# dzik0.net
KiCad netlist of a schematic drawn in EAGLE
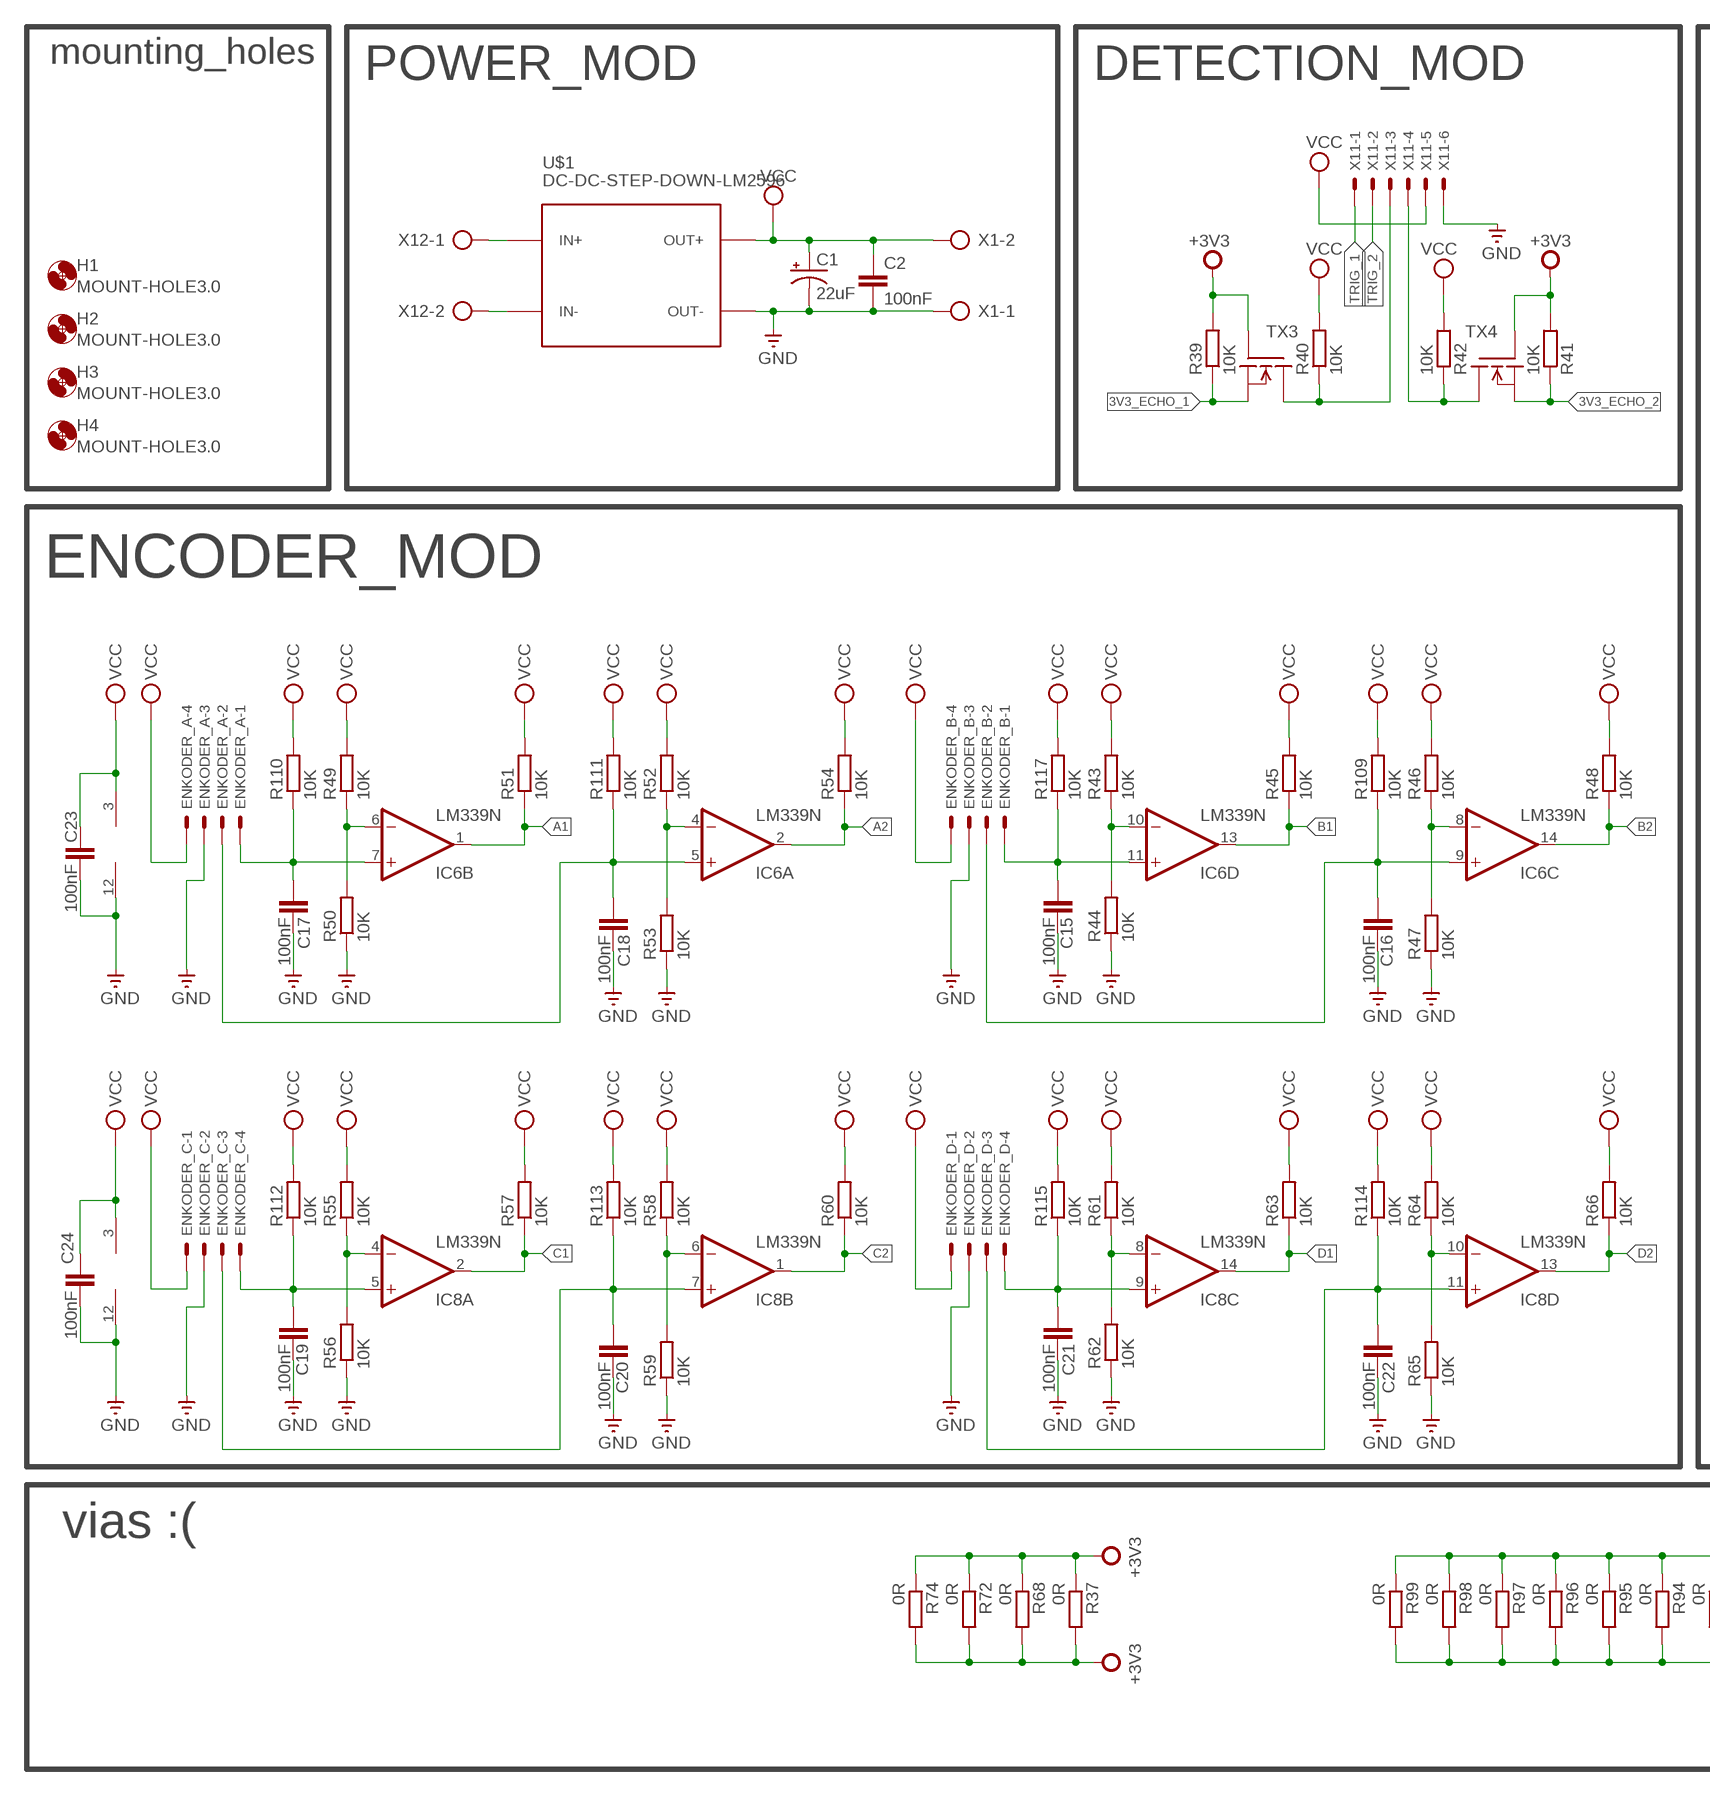
[diagram p0: schematic, sheet 1, part 1 of 2]
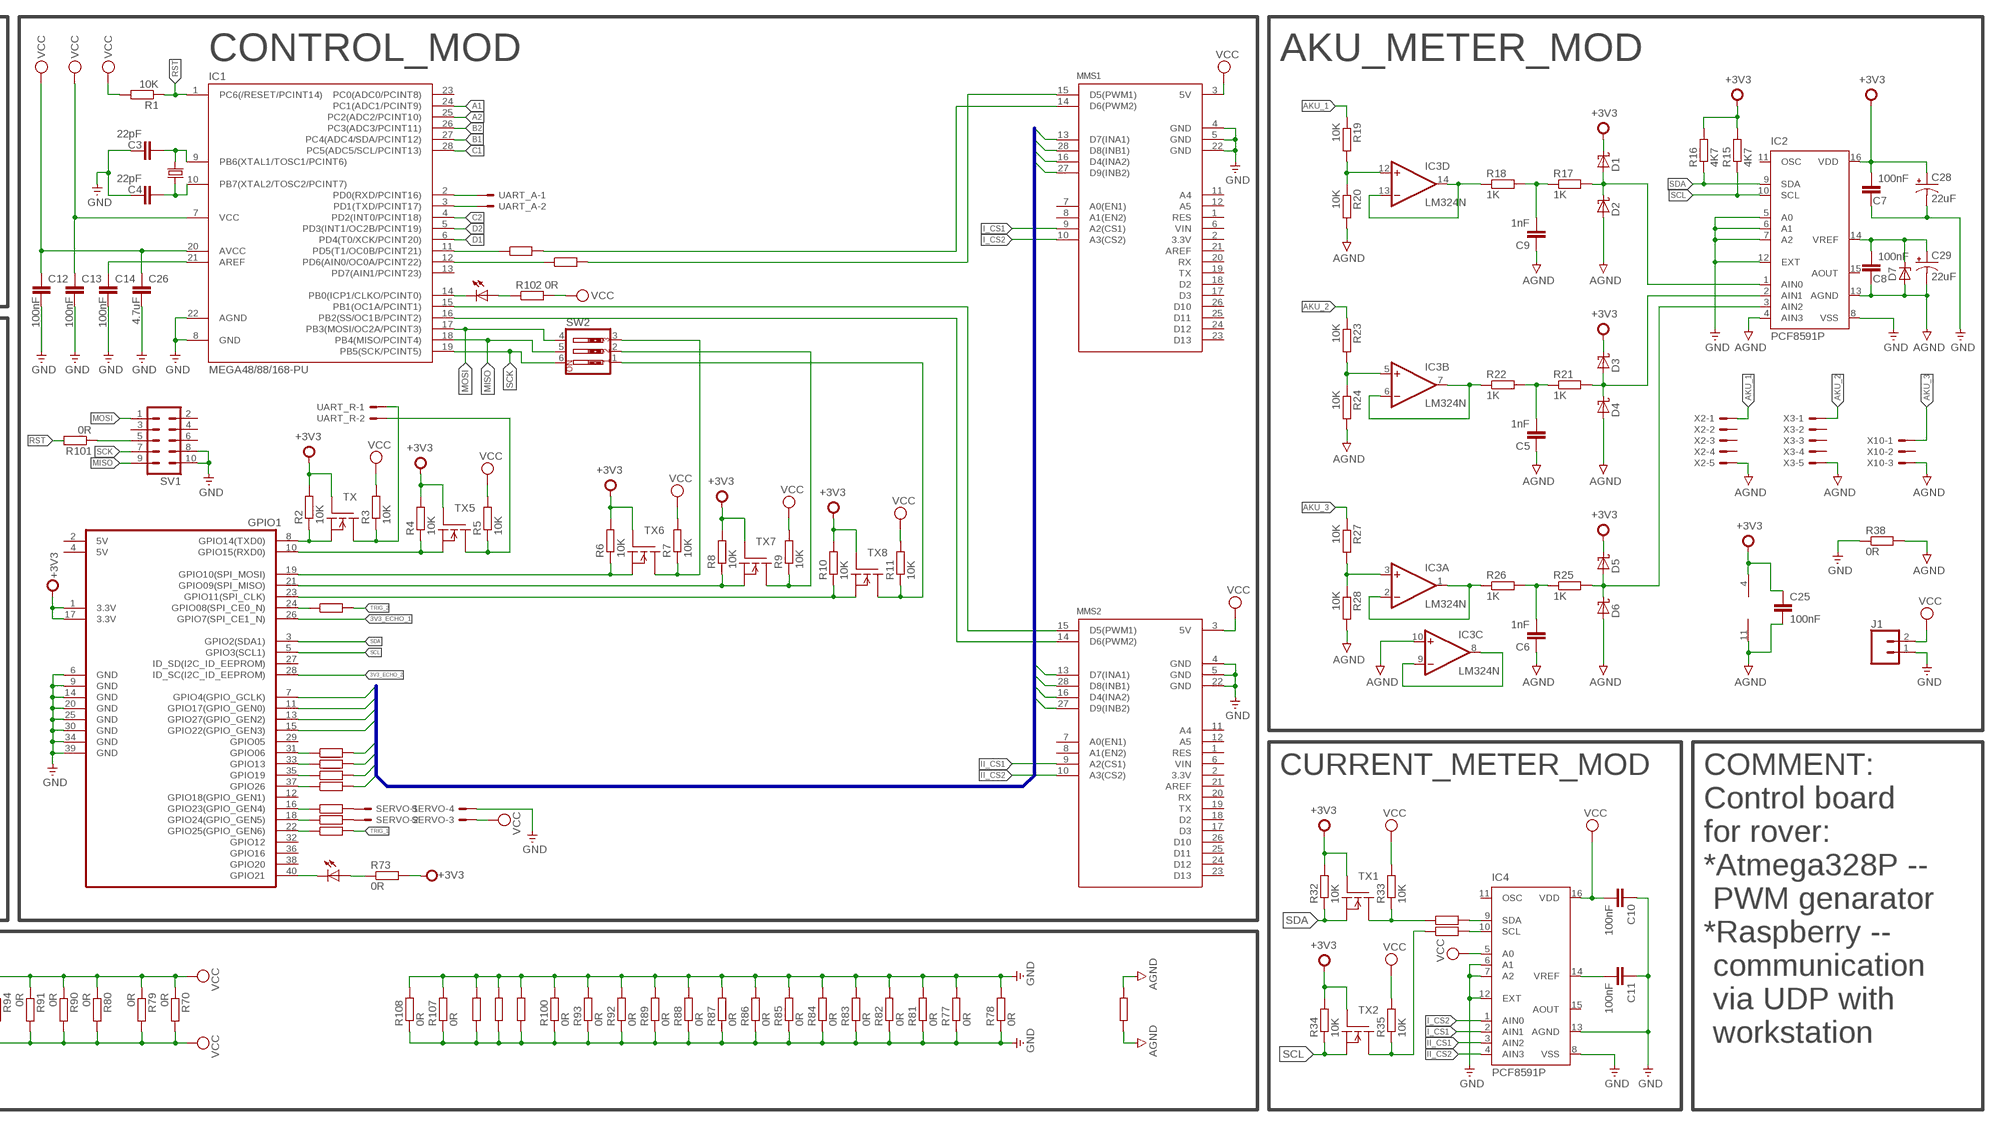
[diagram p1: schematic, sheet 1, part 2 of 2]

(export (version "E")
  (design (tool "Eeschema 10.0.6"))
  (components
    (comp (ref "C1")
      (value "22uF")
      (footprint "eagle-import:E2,5-6")
      (libsource (lib "eagle-import") (part "CPOL-USE2.5-6"))
    )
    (comp (ref "C2")
      (value "100nF")
      (footprint "eagle-import:C025-024X044")
      (libsource (lib "eagle-import") (part "C-EU025-024X044"))
    )
    (comp (ref "C3")
      (value "22pF")
      (footprint "eagle-import:C025-024X044")
      (libsource (lib "eagle-import") (part "C-EU025-024X044"))
    )
    (comp (ref "C4")
      (value "22pF")
      (footprint "eagle-import:C025-024X044")
      (libsource (lib "eagle-import") (part "C-EU025-024X044"))
    )
    (comp (ref "C5")
      (value "1nF")
      (footprint "eagle-import:C025-024X044")
      (libsource (lib "eagle-import") (part "C-EU025-024X044"))
    )
    (comp (ref "C6")
      (value "1nF")
      (footprint "eagle-import:C025-024X044")
      (libsource (lib "eagle-import") (part "C-EU025-024X044"))
    )
    (comp (ref "C7")
      (value "100nF")
      (footprint "eagle-import:C025-024X044")
      (libsource (lib "eagle-import") (part "C-EU025-024X044"))
    )
    (comp (ref "C8")
      (value "100nF")
      (footprint "eagle-import:C025-024X044")
      (libsource (lib "eagle-import") (part "C-EU025-024X044"))
    )
    (comp (ref "C9")
      (value "1nF")
      (footprint "eagle-import:C025-024X044")
      (libsource (lib "eagle-import") (part "C-EU025-024X044"))
    )
    (comp (ref "C10")
      (value "100nF")
      (footprint "eagle-import:C025-024X044")
      (libsource (lib "eagle-import") (part "C-EU025-024X044"))
    )
    (comp (ref "C11")
      (value "100nF")
      (footprint "eagle-import:C025-024X044")
      (libsource (lib "eagle-import") (part "C-EU025-024X044"))
    )
    (comp (ref "C12")
      (value "100nF")
      (footprint "eagle-import:C025-024X044")
      (libsource (lib "eagle-import") (part "C-EU025-024X044"))
    )
    (comp (ref "C13")
      (value "100nF")
      (footprint "eagle-import:C025-024X044")
      (libsource (lib "eagle-import") (part "C-EU025-024X044"))
    )
    (comp (ref "C14")
      (value "100nF")
      (footprint "eagle-import:C025-024X044")
      (libsource (lib "eagle-import") (part "C-EU025-024X044"))
    )
    (comp (ref "C15")
      (value "100nF")
      (footprint "eagle-import:C025-024X044")
      (libsource (lib "eagle-import") (part "C-EU025-024X044"))
    )
    (comp (ref "C16")
      (value "100nF")
      (footprint "eagle-import:C025-024X044")
      (libsource (lib "eagle-import") (part "C-EU025-024X044"))
    )
    (comp (ref "C17")
      (value "100nF")
      (footprint "eagle-import:C025-024X044")
      (libsource (lib "eagle-import") (part "C-EU025-024X044"))
    )
    (comp (ref "C18")
      (value "100nF")
      (footprint "eagle-import:C025-024X044")
      (libsource (lib "eagle-import") (part "C-EU025-024X044"))
    )
    (comp (ref "C19")
      (value "100nF")
      (footprint "eagle-import:C025-024X044")
      (libsource (lib "eagle-import") (part "C-EU025-024X044"))
    )
    (comp (ref "C20")
      (value "100nF")
      (footprint "eagle-import:C025-024X044")
      (libsource (lib "eagle-import") (part "C-EU025-024X044"))
    )
    (comp (ref "C21")
      (value "100nF")
      (footprint "eagle-import:C025-024X044")
      (libsource (lib "eagle-import") (part "C-EU025-024X044"))
    )
    (comp (ref "C22")
      (value "100nF")
      (footprint "eagle-import:C025-024X044")
      (libsource (lib "eagle-import") (part "C-EU025-024X044"))
    )
    (comp (ref "C23")
      (value "100nF")
      (footprint "eagle-import:C025-024X044")
      (libsource (lib "eagle-import") (part "C-EU025-024X044"))
    )
    (comp (ref "C24")
      (value "100nF")
      (footprint "eagle-import:C025-024X044")
      (libsource (lib "eagle-import") (part "C-EU025-024X044"))
    )
    (comp (ref "C25")
      (value "100nF")
      (footprint "eagle-import:C025-024X044")
      (libsource (lib "eagle-import") (part "C-EU025-024X044"))
    )
    (comp (ref "C26")
      (value "4.7uF")
      (footprint "eagle-import:C050-025X075")
      (libsource (lib "eagle-import") (part "C-EU050-025X075"))
    )
    (comp (ref "C28")
      (value "22uF")
      (footprint "eagle-import:E2,5-6")
      (libsource (lib "eagle-import") (part "CPOL-USE2.5-6"))
    )
    (comp (ref "C29")
      (value "22uF")
      (footprint "eagle-import:E2,5-6")
      (libsource (lib "eagle-import") (part "CPOL-USE2.5-6"))
    )
    (comp (ref "D1")
      (value "SCHOTTKY-DIODEDO35-7")
      (footprint "eagle-import:DO35-7")
      (libsource (lib "eagle-import") (part "SCHOTTKY-DIODEDO35-7"))
    )
    (comp (ref "D2")
      (value "SCHOTTKY-DIODEDO35-7")
      (footprint "eagle-import:DO35-7")
      (libsource (lib "eagle-import") (part "SCHOTTKY-DIODEDO35-7"))
    )
    (comp (ref "D3")
      (value "SCHOTTKY-DIODEDO35-7")
      (footprint "eagle-import:DO35-7")
      (libsource (lib "eagle-import") (part "SCHOTTKY-DIODEDO35-7"))
    )
    (comp (ref "D4")
      (value "SCHOTTKY-DIODEDO35-7")
      (footprint "eagle-import:DO35-7")
      (libsource (lib "eagle-import") (part "SCHOTTKY-DIODEDO35-7"))
    )
    (comp (ref "D5")
      (value "SCHOTTKY-DIODEDO35-7")
      (footprint "eagle-import:DO35-7")
      (libsource (lib "eagle-import") (part "SCHOTTKY-DIODEDO35-7"))
    )
    (comp (ref "D6")
      (value "SCHOTTKY-DIODEDO35-7")
      (footprint "eagle-import:DO35-7")
      (libsource (lib "eagle-import") (part "SCHOTTKY-DIODEDO35-7"))
    )
    (comp (ref "D7")
      (value "ZENER-DIODEZD-5")
      (footprint "eagle-import:ZDIO-5")
      (libsource (lib "eagle-import") (part "ZENER-DIODEZD-5"))
    )
    (comp (ref "ENKODER_A")
      (value "JST-XH-04-PIN-LONG-PAD")
      (footprint "eagle-import:JST-XH-04-PACKAGE-LONG-PAD")
      (libsource (lib "eagle-import") (part "JST-XH-04-PIN-LONG-PAD"))
    )
    (comp (ref "ENKODER_B")
      (value "JST-XH-04-PIN-LONG-PAD")
      (footprint "eagle-import:JST-XH-04-PACKAGE-LONG-PAD")
      (libsource (lib "eagle-import") (part "JST-XH-04-PIN-LONG-PAD"))
    )
    (comp (ref "ENKODER_C")
      (value "JST-XH-04-PIN-LONG-PAD")
      (footprint "eagle-import:JST-XH-04-PACKAGE-LONG-PAD")
      (libsource (lib "eagle-import") (part "JST-XH-04-PIN-LONG-PAD"))
    )
    (comp (ref "ENKODER_D")
      (value "JST-XH-04-PIN-LONG-PAD")
      (footprint "eagle-import:JST-XH-04-PACKAGE-LONG-PAD")
      (libsource (lib "eagle-import") (part "JST-XH-04-PIN-LONG-PAD"))
    )
    (comp (ref "GPIO1")
      (value "_GPIO_RASPBERRY")
      (footprint "eagle-import:GPIO_RASPBERRY")
      (libsource (lib "eagle-import") (part "_GPIO_RASPBERRY"))
    )
    (comp (ref "H1")
      (value "MOUNT-HOLE3.0")
      (footprint "eagle-import:3,0")
      (libsource (lib "eagle-import") (part "MOUNT-HOLE3.0"))
    )
    (comp (ref "H2")
      (value "MOUNT-HOLE3.0")
      (footprint "eagle-import:3,0")
      (libsource (lib "eagle-import") (part "MOUNT-HOLE3.0"))
    )
    (comp (ref "H3")
      (value "MOUNT-HOLE3.0")
      (footprint "eagle-import:3,0")
      (libsource (lib "eagle-import") (part "MOUNT-HOLE3.0"))
    )
    (comp (ref "H4")
      (value "MOUNT-HOLE3.0")
      (footprint "eagle-import:3,0")
      (libsource (lib "eagle-import") (part "MOUNT-HOLE3.0"))
    )
    (comp (ref "IC1")
      (value "MEGA48/88/168-PU")
      (footprint "eagle-import:DIL28-3")
      (libsource (lib "eagle-import") (part "MEGA48/88/168-PU"))
    )
    (comp (ref "IC2")
      (value "PCF8591P")
      (footprint "eagle-import:DIL16")
      (fields (field (name "MF") "FARNELL"))
      (libsource (lib "eagle-import") (part "PCF8591P"))
    )
    (comp (ref "IC3")
      (value "LM324N")
      (footprint "eagle-import:DIL14")
      (libsource (lib "eagle-import") (part "LM324N"))
    )
    (comp (ref "IC4")
      (value "PCF8591P")
      (footprint "eagle-import:DIL16")
      (fields (field (name "MF") "FARNELL"))
      (libsource (lib "eagle-import") (part "PCF8591P"))
    )
    (comp (ref "IC6")
      (value "LM339N")
      (footprint "eagle-import:DIL14")
      (libsource (lib "eagle-import") (part "LM339N"))
    )
    (comp (ref "IC8")
      (value "LM339N")
      (footprint "eagle-import:DIL14")
      (libsource (lib "eagle-import") (part "LM339N"))
    )
    (comp (ref "J1")
      (value "CONN_02")
      (footprint "eagle-import:1X02")
      (libsource (lib "eagle-import") (part "CONN_02"))
    )
    (comp (ref "LED1")
      (value "LED5MM")
      (footprint "eagle-import:LED5MM")
      (libsource (lib "eagle-import") (part "LED5MM"))
    )
    (comp (ref "LED3")
      (value "LED5MM")
      (footprint "eagle-import:LED5MM")
      (libsource (lib "eagle-import") (part "LED5MM"))
    )
    (comp (ref "MMS1")
      (value "MONSTERMOTO_SHIELD")
      (footprint "eagle-import:MONSTER_MOTO_1")
      (libsource (lib "eagle-import") (part "MONSTERMOTO_SHIELD"))
    )
    (comp (ref "MMS2")
      (value "MONSTERMOTO_SHIELD")
      (footprint "eagle-import:MONSTER_MOTO_1")
      (libsource (lib "eagle-import") (part "MONSTERMOTO_SHIELD"))
    )
    (comp (ref "Q1")
      (value "11.520MHz")
      (footprint "eagle-import:HC49_S")
      (libsource (lib "eagle-import") (part "CRYSTALHC49S"))
    )
    (comp (ref "R1")
      (value "10K")
      (footprint "eagle-import:0207_7")
      (libsource (lib "eagle-import") (part "R-EU_0207/7"))
    )
    (comp (ref "R2")
      (value "10K")
      (footprint "eagle-import:0207_7")
      (libsource (lib "eagle-import") (part "R-EU_0207/7"))
    )
    (comp (ref "R3")
      (value "10K")
      (footprint "eagle-import:0207_7")
      (libsource (lib "eagle-import") (part "R-EU_0207/7"))
    )
    (comp (ref "R4")
      (value "10K")
      (footprint "eagle-import:0207_7")
      (libsource (lib "eagle-import") (part "R-EU_0207/7"))
    )
    (comp (ref "R5")
      (value "10K")
      (footprint "eagle-import:0207_7")
      (libsource (lib "eagle-import") (part "R-EU_0207/7"))
    )
    (comp (ref "R6")
      (value "10K")
      (footprint "eagle-import:0207_7")
      (libsource (lib "eagle-import") (part "R-EU_0207/7"))
    )
    (comp (ref "R7")
      (value "10K")
      (footprint "eagle-import:0207_7")
      (libsource (lib "eagle-import") (part "R-EU_0207/7"))
    )
    (comp (ref "R8")
      (value "10K")
      (footprint "eagle-import:0207_7")
      (libsource (lib "eagle-import") (part "R-EU_0207/7"))
    )
    (comp (ref "R9")
      (value "10K")
      (footprint "eagle-import:0207_7")
      (libsource (lib "eagle-import") (part "R-EU_0207/7"))
    )
    (comp (ref "R10")
      (value "10K")
      (footprint "eagle-import:0207_7")
      (libsource (lib "eagle-import") (part "R-EU_0207/7"))
    )
    (comp (ref "R11")
      (value "10K")
      (footprint "eagle-import:0207_7")
      (libsource (lib "eagle-import") (part "R-EU_0207/7"))
    )
    (comp (ref "R12")
      (value "0R")
      (footprint "eagle-import:0207_10")
      (libsource (lib "eagle-import") (part "R-EU_0207/10"))
    )
    (comp (ref "R13")
      (value "0R")
      (footprint "eagle-import:0207_10")
      (libsource (lib "eagle-import") (part "R-EU_0207/10"))
    )
    (comp (ref "R14")
      (value "0R")
      (footprint "eagle-import:0207_10")
      (libsource (lib "eagle-import") (part "R-EU_0207/10"))
    )
    (comp (ref "R15")
      (value "4K7")
      (footprint "eagle-import:0207_7")
      (libsource (lib "eagle-import") (part "R-EU_0207/7"))
    )
    (comp (ref "R16")
      (value "4K7")
      (footprint "eagle-import:0207_7")
      (libsource (lib "eagle-import") (part "R-EU_0207/7"))
    )
    (comp (ref "R17")
      (value "1K")
      (footprint "eagle-import:0207_7")
      (libsource (lib "eagle-import") (part "R-EU_0207/7"))
    )
    (comp (ref "R18")
      (value "1K")
      (footprint "eagle-import:0207_7")
      (libsource (lib "eagle-import") (part "R-EU_0207/7"))
    )
    (comp (ref "R19")
      (value "10K")
      (footprint "eagle-import:0207_7")
      (libsource (lib "eagle-import") (part "R-EU_0207/7"))
    )
    (comp (ref "R20")
      (value "10K")
      (footprint "eagle-import:0207_7")
      (libsource (lib "eagle-import") (part "R-EU_0207/7"))
    )
    (comp (ref "R21")
      (value "1K")
      (footprint "eagle-import:0207_7")
      (libsource (lib "eagle-import") (part "R-EU_0207/7"))
    )
    (comp (ref "R22")
      (value "1K")
      (footprint "eagle-import:0207_7")
      (libsource (lib "eagle-import") (part "R-EU_0207/7"))
    )
    (comp (ref "R23")
      (value "10K")
      (footprint "eagle-import:0207_7")
      (libsource (lib "eagle-import") (part "R-EU_0207/7"))
    )
    (comp (ref "R24")
      (value "10K")
      (footprint "eagle-import:0207_7")
      (libsource (lib "eagle-import") (part "R-EU_0207/7"))
    )
    (comp (ref "R25")
      (value "1K")
      (footprint "eagle-import:0207_7")
      (libsource (lib "eagle-import") (part "R-EU_0207/7"))
    )
    (comp (ref "R26")
      (value "1K")
      (footprint "eagle-import:0207_7")
      (libsource (lib "eagle-import") (part "R-EU_0207/7"))
    )
    (comp (ref "R27")
      (value "10K")
      (footprint "eagle-import:0207_7")
      (libsource (lib "eagle-import") (part "R-EU_0207/7"))
    )
    (comp (ref "R28")
      (value "10K")
      (footprint "eagle-import:0207_7")
      (libsource (lib "eagle-import") (part "R-EU_0207/7"))
    )
    (comp (ref "R29")
      (value "0R")
      (footprint "eagle-import:0204_7")
      (libsource (lib "eagle-import") (part "R-EU_0204/7"))
    )
    (comp (ref "R30")
      (value "0R")
      (footprint "eagle-import:0204_7")
      (libsource (lib "eagle-import") (part "R-EU_0204/7"))
    )
    (comp (ref "R31")
      (value "0R")
      (footprint "eagle-import:0207_7")
      (libsource (lib "eagle-import") (part "R-EU_0207/7"))
    )
    (comp (ref "R32")
      (value "10K")
      (footprint "eagle-import:0207_7")
      (libsource (lib "eagle-import") (part "R-EU_0207/7"))
    )
    (comp (ref "R33")
      (value "10K")
      (footprint "eagle-import:0207_7")
      (libsource (lib "eagle-import") (part "R-EU_0207/7"))
    )
    (comp (ref "R34")
      (value "10K")
      (footprint "eagle-import:0207_7")
      (libsource (lib "eagle-import") (part "R-EU_0207/7"))
    )
    (comp (ref "R35")
      (value "10K")
      (footprint "eagle-import:0207_7")
      (libsource (lib "eagle-import") (part "R-EU_0207/7"))
    )
    (comp (ref "R36")
      (value "0R")
      (footprint "eagle-import:0207_7")
      (libsource (lib "eagle-import") (part "R-EU_0207/7"))
    )
    (comp (ref "R37")
      (value "0R")
      (footprint "eagle-import:0207_7")
      (libsource (lib "eagle-import") (part "R-EU_0207/7"))
    )
    (comp (ref "R38")
      (value "0R")
      (footprint "eagle-import:0207_7")
      (libsource (lib "eagle-import") (part "R-EU_0207/7"))
    )
    (comp (ref "R39")
      (value "10K")
      (footprint "eagle-import:0207_7")
      (libsource (lib "eagle-import") (part "R-EU_0207/7"))
    )
    (comp (ref "R40")
      (value "10K")
      (footprint "eagle-import:0207_7")
      (libsource (lib "eagle-import") (part "R-EU_0207/7"))
    )
    (comp (ref "R41")
      (value "10K")
      (footprint "eagle-import:0207_7")
      (libsource (lib "eagle-import") (part "R-EU_0207/7"))
    )
    (comp (ref "R42")
      (value "10K")
      (footprint "eagle-import:0207_7")
      (libsource (lib "eagle-import") (part "R-EU_0207/7"))
    )
    (comp (ref "R43")
      (value "10K")
      (footprint "eagle-import:0207_7")
      (libsource (lib "eagle-import") (part "R-EU_0207/7"))
    )
    (comp (ref "R44")
      (value "10K")
      (footprint "eagle-import:0207_7")
      (libsource (lib "eagle-import") (part "R-EU_0207/7"))
    )
    (comp (ref "R45")
      (value "10K")
      (footprint "eagle-import:0207_7")
      (libsource (lib "eagle-import") (part "R-EU_0207/7"))
    )
    (comp (ref "R46")
      (value "10K")
      (footprint "eagle-import:0207_7")
      (libsource (lib "eagle-import") (part "R-EU_0207/7"))
    )
    (comp (ref "R47")
      (value "10K")
      (footprint "eagle-import:0207_7")
      (libsource (lib "eagle-import") (part "R-EU_0207/7"))
    )
    (comp (ref "R48")
      (value "10K")
      (footprint "eagle-import:0207_7")
      (libsource (lib "eagle-import") (part "R-EU_0207/7"))
    )
    (comp (ref "R49")
      (value "10K")
      (footprint "eagle-import:0207_7")
      (libsource (lib "eagle-import") (part "R-EU_0207/7"))
    )
    (comp (ref "R50")
      (value "10K")
      (footprint "eagle-import:0207_7")
      (libsource (lib "eagle-import") (part "R-EU_0207/7"))
    )
    (comp (ref "R51")
      (value "10K")
      (footprint "eagle-import:0207_7")
      (libsource (lib "eagle-import") (part "R-EU_0207/7"))
    )
    (comp (ref "R52")
      (value "10K")
      (footprint "eagle-import:0207_7")
      (libsource (lib "eagle-import") (part "R-EU_0207/7"))
    )
    (comp (ref "R53")
      (value "10K")
      (footprint "eagle-import:0207_7")
      (libsource (lib "eagle-import") (part "R-EU_0207/7"))
    )
    (comp (ref "R54")
      (value "10K")
      (footprint "eagle-import:0207_7")
      (libsource (lib "eagle-import") (part "R-EU_0207/7"))
    )
    (comp (ref "R55")
      (value "10K")
      (footprint "eagle-import:0207_7")
      (libsource (lib "eagle-import") (part "R-EU_0207/7"))
    )
    (comp (ref "R56")
      (value "10K")
      (footprint "eagle-import:0207_7")
      (libsource (lib "eagle-import") (part "R-EU_0207/7"))
    )
    (comp (ref "R57")
      (value "10K")
      (footprint "eagle-import:0207_7")
      (libsource (lib "eagle-import") (part "R-EU_0207/7"))
    )
    (comp (ref "R58")
      (value "10K")
      (footprint "eagle-import:0207_7")
      (libsource (lib "eagle-import") (part "R-EU_0207/7"))
    )
    (comp (ref "R59")
      (value "10K")
      (footprint "eagle-import:0207_7")
      (libsource (lib "eagle-import") (part "R-EU_0207/7"))
    )
    (comp (ref "R60")
      (value "10K")
      (footprint "eagle-import:0207_7")
      (libsource (lib "eagle-import") (part "R-EU_0207/7"))
    )
    (comp (ref "R61")
      (value "10K")
      (footprint "eagle-import:0207_7")
      (libsource (lib "eagle-import") (part "R-EU_0207/7"))
    )
    (comp (ref "R62")
      (value "10K")
      (footprint "eagle-import:0207_7")
      (libsource (lib "eagle-import") (part "R-EU_0207/7"))
    )
    (comp (ref "R63")
      (value "10K")
      (footprint "eagle-import:0207_7")
      (libsource (lib "eagle-import") (part "R-EU_0207/7"))
    )
    (comp (ref "R64")
      (value "10K")
      (footprint "eagle-import:0207_7")
      (libsource (lib "eagle-import") (part "R-EU_0207/7"))
    )
    (comp (ref "R65")
      (value "10K")
      (footprint "eagle-import:0207_7")
      (libsource (lib "eagle-import") (part "R-EU_0207/7"))
    )
    (comp (ref "R66")
      (value "10K")
      (footprint "eagle-import:0207_7")
      (libsource (lib "eagle-import") (part "R-EU_0207/7"))
    )
    (comp (ref "R67")
      (value "0R")
      (footprint "eagle-import:0207_10")
      (libsource (lib "eagle-import") (part "R-EU_0207/10"))
    )
    (comp (ref "R68")
      (value "0R")
      (footprint "eagle-import:0207_7")
      (libsource (lib "eagle-import") (part "R-EU_0207/7"))
    )
    (comp (ref "R69")
      (value "0R")
      (footprint "eagle-import:0207_10")
      (libsource (lib "eagle-import") (part "R-EU_0207/10"))
    )
    (comp (ref "R70")
      (value "0R")
      (footprint "eagle-import:0207_10")
      (libsource (lib "eagle-import") (part "R-EU_0207/10"))
    )
    (comp (ref "R71")
      (value "0R")
      (footprint "eagle-import:0207_10")
      (libsource (lib "eagle-import") (part "R-EU_0207/10"))
    )
    (comp (ref "R72")
      (value "0R")
      (footprint "eagle-import:0207_7")
      (libsource (lib "eagle-import") (part "R-EU_0207/7"))
    )
    (comp (ref "R73")
      (value "0R")
      (footprint "eagle-import:0207_7")
      (libsource (lib "eagle-import") (part "R-EU_0207/7"))
    )
    (comp (ref "R74")
      (value "0R")
      (footprint "eagle-import:0207_7")
      (libsource (lib "eagle-import") (part "R-EU_0207/7"))
    )
    (comp (ref "R75")
      (value "0R")
      (footprint "eagle-import:0204_7")
      (libsource (lib "eagle-import") (part "R-EU_0204/7"))
    )
    (comp (ref "R76")
      (value "0R")
      (footprint "eagle-import:0204_7")
      (libsource (lib "eagle-import") (part "R-EU_0204/7"))
    )
    (comp (ref "R77")
      (value "0R")
      (footprint "eagle-import:0207_7")
      (libsource (lib "eagle-import") (part "R-EU_0207/7"))
    )
    (comp (ref "R78")
      (value "0R")
      (footprint "eagle-import:0207_7")
      (libsource (lib "eagle-import") (part "R-EU_0207/7"))
    )
    (comp (ref "R79")
      (value "0R")
      (footprint "eagle-import:0207_7")
      (libsource (lib "eagle-import") (part "R-EU_0207/7"))
    )
    (comp (ref "R80")
      (value "0R")
      (footprint "eagle-import:0207_7")
      (libsource (lib "eagle-import") (part "R-EU_0207/7"))
    )
    (comp (ref "R81")
      (value "0R")
      (footprint "eagle-import:0207_7")
      (libsource (lib "eagle-import") (part "R-EU_0207/7"))
    )
    (comp (ref "R82")
      (value "0R")
      (footprint "eagle-import:0207_7")
      (libsource (lib "eagle-import") (part "R-EU_0207/7"))
    )
    (comp (ref "R83")
      (value "0R")
      (footprint "eagle-import:0207_7")
      (libsource (lib "eagle-import") (part "R-EU_0207/7"))
    )
    (comp (ref "R84")
      (value "0R")
      (footprint "eagle-import:0207_7")
      (libsource (lib "eagle-import") (part "R-EU_0207/7"))
    )
    (comp (ref "R85")
      (value "0R")
      (footprint "eagle-import:0207_7")
      (libsource (lib "eagle-import") (part "R-EU_0207/7"))
    )
    (comp (ref "R86")
      (value "0R")
      (footprint "eagle-import:0207_7")
      (libsource (lib "eagle-import") (part "R-EU_0207/7"))
    )
    (comp (ref "R87")
      (value "0R")
      (footprint "eagle-import:0207_7")
      (libsource (lib "eagle-import") (part "R-EU_0207/7"))
    )
    (comp (ref "R88")
      (value "0R")
      (footprint "eagle-import:0207_7")
      (libsource (lib "eagle-import") (part "R-EU_0207/7"))
    )
    (comp (ref "R89")
      (value "0R")
      (footprint "eagle-import:0207_7")
      (libsource (lib "eagle-import") (part "R-EU_0207/7"))
    )
    (comp (ref "R90")
      (value "0R")
      (footprint "eagle-import:0207_7")
      (libsource (lib "eagle-import") (part "R-EU_0207/7"))
    )
    (comp (ref "R91")
      (value "0R")
      (footprint "eagle-import:0207_7")
      (libsource (lib "eagle-import") (part "R-EU_0207/7"))
    )
    (comp (ref "R92")
      (value "0R")
      (footprint "eagle-import:0207_7")
      (libsource (lib "eagle-import") (part "R-EU_0207/7"))
    )
    (comp (ref "R93")
      (value "0R")
      (footprint "eagle-import:0207_7")
      (libsource (lib "eagle-import") (part "R-EU_0207/7"))
    )
    (comp (ref "R94")
      (value "0R")
      (footprint "eagle-import:0207_7")
      (libsource (lib "eagle-import") (part "R-EU_0207/7"))
    )
    (comp (ref "R95")
      (value "0R")
      (footprint "eagle-import:0207_7")
      (libsource (lib "eagle-import") (part "R-EU_0207/7"))
    )
    (comp (ref "R96")
      (value "0R")
      (footprint "eagle-import:0207_7")
      (libsource (lib "eagle-import") (part "R-EU_0207/7"))
    )
    (comp (ref "R97")
      (value "0R")
      (footprint "eagle-import:0207_7")
      (libsource (lib "eagle-import") (part "R-EU_0207/7"))
    )
    (comp (ref "R98")
      (value "0R")
      (footprint "eagle-import:0207_7")
      (libsource (lib "eagle-import") (part "R-EU_0207/7"))
    )
    (comp (ref "R99")
      (value "0R")
      (footprint "eagle-import:0207_7")
      (libsource (lib "eagle-import") (part "R-EU_0207/7"))
    )
    (comp (ref "R100")
      (value "0R")
      (footprint "eagle-import:0207_7")
      (libsource (lib "eagle-import") (part "R-EU_0207/7"))
    )
    (comp (ref "R101")
      (value "0R")
      (footprint "eagle-import:0207_7")
      (libsource (lib "eagle-import") (part "R-EU_0207/7"))
    )
    (comp (ref "R102")
      (value "0R")
      (footprint "eagle-import:0207_7")
      (libsource (lib "eagle-import") (part "R-EU_0207/7"))
    )
    (comp (ref "R103")
      (value "0R")
      (footprint "eagle-import:0207_10")
      (libsource (lib "eagle-import") (part "R-EU_0207/10"))
    )
    (comp (ref "R104")
      (value "0R")
      (footprint "eagle-import:0207_10")
      (libsource (lib "eagle-import") (part "R-EU_0207/10"))
    )
    (comp (ref "R105")
      (value "0R")
      (footprint "eagle-import:0207_10")
      (libsource (lib "eagle-import") (part "R-EU_0207/10"))
    )
    (comp (ref "R106")
      (value "0R")
      (footprint "eagle-import:0207_7")
      (libsource (lib "eagle-import") (part "R-EU_0207/7"))
    )
    (comp (ref "R107")
      (value "0R")
      (footprint "eagle-import:0207_7")
      (libsource (lib "eagle-import") (part "R-EU_0207/7"))
    )
    (comp (ref "R108")
      (value "0R")
      (footprint "eagle-import:0207_7")
      (libsource (lib "eagle-import") (part "R-EU_0207/7"))
    )
    (comp (ref "R109")
      (value "10K")
      (footprint "eagle-import:0207_7")
      (libsource (lib "eagle-import") (part "R-EU_0207/7"))
    )
    (comp (ref "R110")
      (value "10K")
      (footprint "eagle-import:0207_7")
      (libsource (lib "eagle-import") (part "R-EU_0207/7"))
    )
    (comp (ref "R111")
      (value "10K")
      (footprint "eagle-import:0207_7")
      (libsource (lib "eagle-import") (part "R-EU_0207/7"))
    )
    (comp (ref "R112")
      (value "10K")
      (footprint "eagle-import:0207_7")
      (libsource (lib "eagle-import") (part "R-EU_0207/7"))
    )
    (comp (ref "R113")
      (value "10K")
      (footprint "eagle-import:0207_7")
      (libsource (lib "eagle-import") (part "R-EU_0207/7"))
    )
    (comp (ref "R114")
      (value "10K")
      (footprint "eagle-import:0207_7")
      (libsource (lib "eagle-import") (part "R-EU_0207/7"))
    )
    (comp (ref "R115")
      (value "10K")
      (footprint "eagle-import:0207_7")
      (libsource (lib "eagle-import") (part "R-EU_0207/7"))
    )
    (comp (ref "R117")
      (value "10K")
      (footprint "eagle-import:0207_7")
      (libsource (lib "eagle-import") (part "R-EU_0207/7"))
    )
    (comp (ref "SERVO")
      (value "JST-XH-04-PIN-LONG-PAD")
      (footprint "eagle-import:JST-XH-04-PACKAGE-LONG-PAD")
      (libsource (lib "eagle-import") (part "JST-XH-04-PIN-LONG-PAD"))
    )
    (comp (ref "SV1")
      (value "MA05-2")
      (footprint "eagle-import:MA05-2")
      (libsource (lib "eagle-import") (part "MA05-2"))
    )
    (comp (ref "SW2")
      (value "SW_DIP-3")
      (footprint "eagle-import:EDG-03")
      (libsource (lib "eagle-import") (part "SW_DIP-3"))
    )
    (comp (ref "TX")
      (value "FQN1N50CI")
      (footprint "eagle-import:TO92-INLINE")
      (libsource (lib "eagle-import") (part "FQN1N50CI"))
    )
    (comp (ref "TX1")
      (value "FQN1N50CI")
      (footprint "eagle-import:TO92-INLINE")
      (libsource (lib "eagle-import") (part "FQN1N50CI"))
    )
    (comp (ref "TX2")
      (value "FQN1N50CI")
      (footprint "eagle-import:TO92-INLINE")
      (libsource (lib "eagle-import") (part "FQN1N50CI"))
    )
    (comp (ref "TX3")
      (value "FQN1N50CI")
      (footprint "eagle-import:TO92-INLINE")
      (libsource (lib "eagle-import") (part "FQN1N50CI"))
    )
    (comp (ref "TX4")
      (value "FQN1N50CI")
      (footprint "eagle-import:TO92-INLINE")
      (libsource (lib "eagle-import") (part "FQN1N50CI"))
    )
    (comp (ref "TX5")
      (value "FQN1N50CI")
      (footprint "eagle-import:TO92-INLINE")
      (libsource (lib "eagle-import") (part "FQN1N50CI"))
    )
    (comp (ref "TX6")
      (value "FQN1N50CI")
      (footprint "eagle-import:TO92-INLINE")
      (libsource (lib "eagle-import") (part "FQN1N50CI"))
    )
    (comp (ref "TX7")
      (value "FQN1N50CI")
      (footprint "eagle-import:TO92-INLINE")
      (libsource (lib "eagle-import") (part "FQN1N50CI"))
    )
    (comp (ref "TX8")
      (value "FQN1N50CI")
      (footprint "eagle-import:TO92-INLINE")
      (libsource (lib "eagle-import") (part "FQN1N50CI"))
    )
    (comp (ref "U$1")
      (value "DC-DC-STEP-DOWN-LM2596")
      (footprint "eagle-import:DC-DC-STEP-DOWN-LM2596")
      (libsource (lib "eagle-import") (part "DC-DC-STEP-DOWN-LM2596"))
    )
    (comp (ref "UART_A")
      (value "JST-XH-02-PIN-LONG-PAD")
      (footprint "eagle-import:JST-XH-02-PACKAGE-LONG-PAD")
      (libsource (lib "eagle-import") (part "JST-XH-02-PIN-LONG-PAD"))
    )
    (comp (ref "UART_R")
      (value "JST-XH-02-PIN-LONG-PAD")
      (footprint "eagle-import:JST-XH-02-PACKAGE-LONG-PAD")
      (libsource (lib "eagle-import") (part "JST-XH-02-PIN-LONG-PAD"))
    )
    (comp (ref "X1")
      (value "AK300/2")
      (footprint "eagle-import:AK300_2")
      (libsource (lib "eagle-import") (part "AK300/2"))
    )
    (comp (ref "X2")
      (value "JST-XH-05-PIN-LONG-PAD")
      (footprint "eagle-import:JST-XH-05-PACKAGE-LONG-PAD")
      (libsource (lib "eagle-import") (part "JST-XH-05-PIN-LONG-PAD"))
    )
    (comp (ref "X3")
      (value "JST-XH-05-PIN-LONG-PAD")
      (footprint "eagle-import:JST-XH-05-PACKAGE-LONG-PAD")
      (libsource (lib "eagle-import") (part "JST-XH-05-PIN-LONG-PAD"))
    )
    (comp (ref "X10")
      (value "JST-XH-03-PIN-LONG-PAD")
      (footprint "eagle-import:JST-XH-03-PACKAGE-LONG-PAD")
      (libsource (lib "eagle-import") (part "JST-XH-03-PIN-LONG-PAD"))
    )
    (comp (ref "X11")
      (value "JST-XH-06-PIN-LONG-PAD")
      (footprint "eagle-import:JST-XH-06-PACKAGE-LONG-PAD")
      (libsource (lib "eagle-import") (part "JST-XH-06-PIN-LONG-PAD"))
    )
    (comp (ref "X12")
      (value "AK300/2")
      (footprint "eagle-import:AK300_2")
      (libsource (lib "eagle-import") (part "AK300/2"))
    )
  )
  (nets
    (net (code "1") (name "+3V3") (class "Default")
      (node (ref "C25") (pin "1") (pinfunction "1_1") (pintype "passive"))
      (node (ref "C28") (pin "+") (pinfunction "+_+") (pintype "passive"))
      (node (ref "C7") (pin "2") (pinfunction "2_2") (pintype "passive"))
      (node (ref "D1") (pin "C") (pinfunction "C_C") (pintype "passive"))
      (node (ref "D3") (pin "C") (pinfunction "C_C") (pintype "passive"))
      (node (ref "D5") (pin "C") (pinfunction "C_C") (pintype "passive"))
      (node (ref "GPIO1") (pin "1") (pinfunction "3.3V_1") (pintype "bidirectional"))
      (node (ref "GPIO1") (pin "17") (pinfunction "3.3V_17") (pintype "bidirectional"))
      (node (ref "IC2") (pin "16") (pinfunction "VDD_16") (pintype "power_in"))
      (node (ref "IC3") (pin "4") (pinfunction "V+_4") (pintype "power_in"))
      (node (ref "R10") (pin "2") (pinfunction "2_2") (pintype "passive"))
      (node (ref "R15") (pin "2") (pinfunction "2_2") (pintype "passive"))
      (node (ref "R16") (pin "2") (pinfunction "2_2") (pintype "passive"))
      (node (ref "R2") (pin "2") (pinfunction "2_2") (pintype "passive"))
      (node (ref "R32") (pin "2") (pinfunction "2_2") (pintype "passive"))
      (node (ref "R34") (pin "2") (pinfunction "2_2") (pintype "passive"))
      (node (ref "R37") (pin "1") (pinfunction "1_1") (pintype "passive"))
      (node (ref "R37") (pin "2") (pinfunction "2_2") (pintype "passive"))
      (node (ref "R39") (pin "2") (pinfunction "2_2") (pintype "passive"))
      (node (ref "R4") (pin "2") (pinfunction "2_2") (pintype "passive"))
      (node (ref "R41") (pin "2") (pinfunction "2_2") (pintype "passive"))
      (node (ref "R6") (pin "2") (pinfunction "2_2") (pintype "passive"))
      (node (ref "R68") (pin "1") (pinfunction "1_1") (pintype "passive"))
      (node (ref "R68") (pin "2") (pinfunction "2_2") (pintype "passive"))
      (node (ref "R72") (pin "1") (pinfunction "1_1") (pintype "passive"))
      (node (ref "R72") (pin "2") (pinfunction "2_2") (pintype "passive"))
      (node (ref "R73") (pin "2") (pinfunction "2_2") (pintype "passive"))
      (node (ref "R74") (pin "1") (pinfunction "1_1") (pintype "passive"))
      (node (ref "R74") (pin "2") (pinfunction "2_2") (pintype "passive"))
      (node (ref "R8") (pin "2") (pinfunction "2_2") (pintype "passive"))
      (node (ref "TX") (pin "2") (pinfunction "G_2") (pintype "passive"))
      (node (ref "TX1") (pin "2") (pinfunction "G_2") (pintype "passive"))
      (node (ref "TX2") (pin "2") (pinfunction "G_2") (pintype "passive"))
      (node (ref "TX3") (pin "2") (pinfunction "G_2") (pintype "passive"))
      (node (ref "TX4") (pin "2") (pinfunction "G_2") (pintype "passive"))
      (node (ref "TX5") (pin "2") (pinfunction "G_2") (pintype "passive"))
      (node (ref "TX6") (pin "2") (pinfunction "G_2") (pintype "passive"))
      (node (ref "TX7") (pin "2") (pinfunction "G_2") (pintype "passive"))
      (node (ref "TX8") (pin "2") (pinfunction "G_2") (pintype "passive"))
    )
    (net (code "2") (name "/II_D4") (class "Default")
      (node (ref "GPIO1") (pin "15") (pinfunction "GPIO22(GPIO_GEN3)_15") (pintype "bidirectional"))
      (node (ref "MMS2") (pin "16") (pinfunction "D4(INA2)_16") (pintype "bidirectional"))
    )
    (net (code "3") (name "/II_D7") (class "Default")
      (node (ref "GPIO1") (pin "13") (pinfunction "GPIO27(GPIO_GEN2)_13") (pintype "bidirectional"))
      (node (ref "MMS2") (pin "13") (pinfunction "D7(INA1)_13") (pintype "bidirectional"))
    )
    (net (code "4") (name "/II_D8") (class "Default")
      (node (ref "GPIO1") (pin "11") (pinfunction "GPIO17(GPIO_GEN0)_11") (pintype "bidirectional"))
      (node (ref "MMS2") (pin "28") (pinfunction "D8(INB1)_28") (pintype "bidirectional"))
    )
    (net (code "5") (name "/II_D9") (class "Default")
      (node (ref "GPIO1") (pin "7") (pinfunction "GPIO4(GPIO_GCLK)_7") (pintype "bidirectional"))
      (node (ref "MMS2") (pin "27") (pinfunction "D9(INB2)_27") (pintype "bidirectional"))
    )
    (net (code "6") (name "/I_D4") (class "Default")
      (node (ref "MMS1") (pin "16") (pinfunction "D4(INA2)_16") (pintype "bidirectional"))
      (node (ref "R14") (pin "2") (pinfunction "2_2") (pintype "passive"))
    )
    (net (code "7") (name "/I_D7") (class "Default")
      (node (ref "MMS1") (pin "13") (pinfunction "D7(INA1)_13") (pintype "bidirectional"))
      (node (ref "R67") (pin "2") (pinfunction "2_2") (pintype "passive"))
    )
    (net (code "8") (name "/I_D8") (class "Default")
      (node (ref "MMS1") (pin "28") (pinfunction "D8(INB1)_28") (pintype "bidirectional"))
      (node (ref "R69") (pin "2") (pinfunction "2_2") (pintype "passive"))
    )
    (net (code "9") (name "/I_D9") (class "Default")
      (node (ref "MMS1") (pin "27") (pinfunction "D9(INB2)_27") (pintype "bidirectional"))
      (node (ref "R71") (pin "2") (pinfunction "2_2") (pintype "passive"))
    )
    (net (code "10") (name "3V3_ECHO_1") (class "Default")
      (node (ref "GPIO1") (pin "26") (pinfunction "GPIO7(SPI_CE1_N)_26") (pintype "bidirectional"))
      (node (ref "R39") (pin "1") (pinfunction "1_1") (pintype "passive"))
      (node (ref "TX3") (pin "3") (pinfunction "S_3") (pintype "passive"))
    )
    (net (code "11") (name "3V3_ECHO_2") (class "Default")
      (node (ref "GPIO1") (pin "28") (pinfunction "ID_SC(I2C_ID_EEPROM)_28") (pintype "bidirectional"))
      (node (ref "R41") (pin "1") (pinfunction "1_1") (pintype "passive"))
      (node (ref "TX4") (pin "3") (pinfunction "S_3") (pintype "passive"))
    )
    (net (code "12") (name "A1") (class "Default")
      (node (ref "IC1") (pin "24") (pinfunction "PC1(ADC1/PCINT9)_24") (pintype "bidirectional"))
      (node (ref "IC6") (pin "1") (pinfunction "OUT_1") (pintype "open_collector"))
      (node (ref "R51") (pin "1") (pinfunction "1_1") (pintype "passive"))
    )
    (net (code "13") (name "A2") (class "Default")
      (node (ref "IC1") (pin "25") (pinfunction "PC2(ADC2/PCINT10)_25") (pintype "bidirectional"))
      (node (ref "IC6") (pin "2") (pinfunction "OUT_2") (pintype "open_collector"))
      (node (ref "R54") (pin "1") (pinfunction "1_1") (pintype "passive"))
    )
    (net (code "14") (name "AGND") (class "Default")
      (node (ref "C25") (pin "2") (pinfunction "2_2") (pintype "passive"))
      (node (ref "C29") (pin "-") (pinfunction "-_-") (pintype "passive"))
      (node (ref "C5") (pin "1") (pinfunction "1_1") (pintype "passive"))
      (node (ref "C6") (pin "1") (pinfunction "1_1") (pintype "passive"))
      (node (ref "C8") (pin "1") (pinfunction "1_1") (pintype "passive"))
      (node (ref "C9") (pin "1") (pinfunction "1_1") (pintype "passive"))
      (node (ref "D2") (pin "A") (pinfunction "A_A") (pintype "passive"))
      (node (ref "D4") (pin "A") (pinfunction "A_A") (pintype "passive"))
      (node (ref "D6") (pin "A") (pinfunction "A_A") (pintype "passive"))
      (node (ref "D7") (pin "A") (pinfunction "A_A") (pintype "passive"))
      (node (ref "IC2") (pin "13") (pinfunction "AGND_13") (pintype "power_in"))
      (node (ref "IC2") (pin "4") (pinfunction "AIN3_4") (pintype "input"))
      (node (ref "IC3") (pin "10") (pinfunction "+IN_10") (pintype "input"))
      (node (ref "IC3") (pin "11") (pinfunction "V-_11") (pintype "power_in"))
      (node (ref "R106") (pin "1") (pinfunction "1_1") (pintype "passive"))
      (node (ref "R106") (pin "2") (pinfunction "2_2") (pintype "passive"))
      (node (ref "R20") (pin "2") (pinfunction "2_2") (pintype "passive"))
      (node (ref "R24") (pin "2") (pinfunction "2_2") (pintype "passive"))
      (node (ref "R28") (pin "2") (pinfunction "2_2") (pintype "passive"))
      (node (ref "R38") (pin "2") (pinfunction "2_2") (pintype "passive"))
      (node (ref "X10") (pin "3") (pinfunction "S_3") (pintype "passive"))
      (node (ref "X2") (pin "5") (pinfunction "S_5") (pintype "passive"))
      (node (ref "X3") (pin "5") (pinfunction "S_5") (pintype "passive"))
    )
    (net (code "15") (name "AKU_1") (class "Default")
      (node (ref "R19") (pin "1") (pinfunction "1_1") (pintype "passive"))
      (node (ref "X2") (pin "1") (pinfunction "S_1") (pintype "passive"))
    )
    (net (code "16") (name "AKU_2") (class "Default")
      (node (ref "R23") (pin "1") (pinfunction "1_1") (pintype "passive"))
      (node (ref "X3") (pin "1") (pinfunction "S_1") (pintype "passive"))
    )
    (net (code "17") (name "AKU_3") (class "Default")
      (node (ref "R27") (pin "1") (pinfunction "1_1") (pintype "passive"))
      (node (ref "X10") (pin "1") (pinfunction "S_1") (pintype "passive"))
    )
    (net (code "18") (name "B1") (class "Default")
      (node (ref "IC1") (pin "27") (pinfunction "PC4(ADC4/SDA/PCINT12)_27") (pintype "bidirectional"))
      (node (ref "IC6") (pin "13") (pinfunction "OUT_13") (pintype "open_collector"))
      (node (ref "R45") (pin "1") (pinfunction "1_1") (pintype "passive"))
    )
    (net (code "19") (name "B2") (class "Default")
      (node (ref "IC1") (pin "26") (pinfunction "PC3(ADC3/PCINT11)_26") (pintype "bidirectional"))
      (node (ref "IC6") (pin "14") (pinfunction "OUT_14") (pintype "open_collector"))
      (node (ref "R48") (pin "1") (pinfunction "1_1") (pintype "passive"))
    )
    (net (code "20") (name "C1") (class "Default")
      (node (ref "IC1") (pin "28") (pinfunction "PC5(ADC5/SCL/PCINT13)_28") (pintype "bidirectional"))
      (node (ref "IC8") (pin "2") (pinfunction "OUT_2") (pintype "open_collector"))
      (node (ref "R57") (pin "1") (pinfunction "1_1") (pintype "passive"))
    )
    (net (code "21") (name "C2") (class "Default")
      (node (ref "IC1") (pin "4") (pinfunction "PD2(INT0/PCINT18)_4") (pintype "bidirectional"))
      (node (ref "IC8") (pin "1") (pinfunction "OUT_1") (pintype "open_collector"))
      (node (ref "R60") (pin "1") (pinfunction "1_1") (pintype "passive"))
    )
    (net (code "22") (name "D1") (class "Default")
      (node (ref "IC1") (pin "6") (pinfunction "PD4(T0/XCK/PCINT20)_6") (pintype "bidirectional"))
      (node (ref "IC8") (pin "14") (pinfunction "OUT_14") (pintype "open_collector"))
      (node (ref "R63") (pin "1") (pinfunction "1_1") (pintype "passive"))
    )
    (net (code "23") (name "D2") (class "Default")
      (node (ref "IC1") (pin "5") (pinfunction "PD3(INT1/OC2B/PCINT19)_5") (pintype "bidirectional"))
      (node (ref "IC8") (pin "13") (pinfunction "OUT_13") (pintype "open_collector"))
      (node (ref "R66") (pin "1") (pinfunction "1_1") (pintype "passive"))
    )
    (net (code "24") (name "GND") (class "Default")
      (node (ref "C1") (pin "-") (pinfunction "-_-") (pintype "passive"))
      (node (ref "C10") (pin "1") (pinfunction "1_1") (pintype "passive"))
      (node (ref "C11") (pin "1") (pinfunction "1_1") (pintype "passive"))
      (node (ref "C12") (pin "2") (pinfunction "2_2") (pintype "passive"))
      (node (ref "C13") (pin "2") (pinfunction "2_2") (pintype "passive"))
      (node (ref "C14") (pin "2") (pinfunction "2_2") (pintype "passive"))
      (node (ref "C15") (pin "2") (pinfunction "2_2") (pintype "passive"))
      (node (ref "C16") (pin "2") (pinfunction "2_2") (pintype "passive"))
      (node (ref "C17") (pin "2") (pinfunction "2_2") (pintype "passive"))
      (node (ref "C18") (pin "2") (pinfunction "2_2") (pintype "passive"))
      (node (ref "C19") (pin "2") (pinfunction "2_2") (pintype "passive"))
      (node (ref "C2") (pin "2") (pinfunction "2_2") (pintype "passive"))
      (node (ref "C20") (pin "2") (pinfunction "2_2") (pintype "passive"))
      (node (ref "C21") (pin "2") (pinfunction "2_2") (pintype "passive"))
      (node (ref "C22") (pin "2") (pinfunction "2_2") (pintype "passive"))
      (node (ref "C23") (pin "2") (pinfunction "2_2") (pintype "passive"))
      (node (ref "C24") (pin "2") (pinfunction "2_2") (pintype "passive"))
      (node (ref "C26") (pin "2") (pinfunction "2_2") (pintype "passive"))
      (node (ref "C28") (pin "-") (pinfunction "-_-") (pintype "passive"))
      (node (ref "C3") (pin "1") (pinfunction "1_1") (pintype "passive"))
      (node (ref "C4") (pin "1") (pinfunction "1_1") (pintype "passive"))
      (node (ref "C7") (pin "1") (pinfunction "1_1") (pintype "passive"))
      (node (ref "ENKODER_A") (pin "3") (pinfunction "S_3") (pintype "passive"))
      (node (ref "ENKODER_B") (pin "3") (pinfunction "S_3") (pintype "passive"))
      (node (ref "ENKODER_C") (pin "2") (pinfunction "S_2") (pintype "passive"))
      (node (ref "ENKODER_D") (pin "2") (pinfunction "S_2") (pintype "passive"))
      (node (ref "GPIO1") (pin "14") (pinfunction "GND_14") (pintype "bidirectional"))
      (node (ref "GPIO1") (pin "20") (pinfunction "GND_20") (pintype "bidirectional"))
      (node (ref "GPIO1") (pin "25") (pinfunction "GND_25") (pintype "bidirectional"))
      (node (ref "GPIO1") (pin "30") (pinfunction "GND_30") (pintype "bidirectional"))
      (node (ref "GPIO1") (pin "34") (pinfunction "GND_34") (pintype "bidirectional"))
      (node (ref "GPIO1") (pin "39") (pinfunction "GND_39") (pintype "bidirectional"))
      (node (ref "GPIO1") (pin "6") (pinfunction "GND_6") (pintype "bidirectional"))
      (node (ref "GPIO1") (pin "9") (pinfunction "GND_9") (pintype "bidirectional"))
      (node (ref "IC1") (pin "22") (pinfunction "AGND_22") (pintype "power_in"))
      (node (ref "IC1") (pin "8") (pinfunction "GND_8") (pintype "power_in"))
      (node (ref "IC2") (pin "12") (pinfunction "EXT_12") (pintype "input"))
      (node (ref "IC2") (pin "5") (pinfunction "A0_5") (pintype "input"))
      (node (ref "IC2") (pin "6") (pinfunction "A1_6") (pintype "input"))
      (node (ref "IC2") (pin "7") (pinfunction "A2_7") (pintype "input"))
      (node (ref "IC2") (pin "8") (pinfunction "VSS_8") (pintype "power_in"))
      (node (ref "IC4") (pin "12") (pinfunction "EXT_12") (pintype "input"))
      (node (ref "IC4") (pin "13") (pinfunction "AGND_13") (pintype "power_in"))
      (node (ref "IC4") (pin "6") (pinfunction "A1_6") (pintype "input"))
      (node (ref "IC4") (pin "7") (pinfunction "A2_7") (pintype "input"))
      (node (ref "IC4") (pin "8") (pinfunction "VSS_8") (pintype "power_in"))
      (node (ref "IC6") (pin "12") (pinfunction "GND_12") (pintype "power_in"))
      (node (ref "IC8") (pin "12") (pinfunction "GND_12") (pintype "power_in"))
      (node (ref "J1") (pin "1") (pinfunction "1_1") (pintype "passive"))
      (node (ref "MMS1") (pin "22") (pinfunction "GND_22") (pintype "bidirectional"))
      (node (ref "MMS1") (pin "4") (pinfunction "GND_4") (pintype "bidirectional"))
      (node (ref "MMS1") (pin "5") (pinfunction "GND_5") (pintype "bidirectional"))
      (node (ref "MMS2") (pin "22") (pinfunction "GND_22") (pintype "bidirectional"))
      (node (ref "MMS2") (pin "4") (pinfunction "GND_4") (pintype "bidirectional"))
      (node (ref "MMS2") (pin "5") (pinfunction "GND_5") (pintype "bidirectional"))
      (node (ref "R100") (pin "1") (pinfunction "1_1") (pintype "passive"))
      (node (ref "R100") (pin "2") (pinfunction "2_2") (pintype "passive"))
      (node (ref "R103") (pin "1") (pinfunction "1_1") (pintype "passive"))
      (node (ref "R103") (pin "2") (pinfunction "2_2") (pintype "passive"))
      (node (ref "R104") (pin "1") (pinfunction "1_1") (pintype "passive"))
      (node (ref "R104") (pin "2") (pinfunction "2_2") (pintype "passive"))
      (node (ref "R105") (pin "1") (pinfunction "1_1") (pintype "passive"))
      (node (ref "R105") (pin "2") (pinfunction "2_2") (pintype "passive"))
      (node (ref "R107") (pin "1") (pinfunction "1_1") (pintype "passive"))
      (node (ref "R107") (pin "2") (pinfunction "2_2") (pintype "passive"))
      (node (ref "R108") (pin "1") (pinfunction "1_1") (pintype "passive"))
      (node (ref "R108") (pin "2") (pinfunction "2_2") (pintype "passive"))
      (node (ref "R38") (pin "1") (pinfunction "1_1") (pintype "passive"))
      (node (ref "R44") (pin "1") (pinfunction "1_1") (pintype "passive"))
      (node (ref "R47") (pin "1") (pinfunction "1_1") (pintype "passive"))
      (node (ref "R50") (pin "1") (pinfunction "1_1") (pintype "passive"))
      (node (ref "R53") (pin "1") (pinfunction "1_1") (pintype "passive"))
      (node (ref "R56") (pin "1") (pinfunction "1_1") (pintype "passive"))
      (node (ref "R59") (pin "1") (pinfunction "1_1") (pintype "passive"))
      (node (ref "R62") (pin "1") (pinfunction "1_1") (pintype "passive"))
      (node (ref "R65") (pin "1") (pinfunction "1_1") (pintype "passive"))
      (node (ref "R77") (pin "1") (pinfunction "1_1") (pintype "passive"))
      (node (ref "R77") (pin "2") (pinfunction "2_2") (pintype "passive"))
      (node (ref "R78") (pin "1") (pinfunction "1_1") (pintype "passive"))
      (node (ref "R78") (pin "2") (pinfunction "2_2") (pintype "passive"))
      (node (ref "R81") (pin "1") (pinfunction "1_1") (pintype "passive"))
      (node (ref "R81") (pin "2") (pinfunction "2_2") (pintype "passive"))
      (node (ref "R82") (pin "1") (pinfunction "1_1") (pintype "passive"))
      (node (ref "R82") (pin "2") (pinfunction "2_2") (pintype "passive"))
      (node (ref "R83") (pin "1") (pinfunction "1_1") (pintype "passive"))
      (node (ref "R83") (pin "2") (pinfunction "2_2") (pintype "passive"))
      (node (ref "R84") (pin "1") (pinfunction "1_1") (pintype "passive"))
      (node (ref "R84") (pin "2") (pinfunction "2_2") (pintype "passive"))
      (node (ref "R85") (pin "1") (pinfunction "1_1") (pintype "passive"))
      (node (ref "R85") (pin "2") (pinfunction "2_2") (pintype "passive"))
      (node (ref "R86") (pin "1") (pinfunction "1_1") (pintype "passive"))
      (node (ref "R86") (pin "2") (pinfunction "2_2") (pintype "passive"))
      (node (ref "R87") (pin "1") (pinfunction "1_1") (pintype "passive"))
      (node (ref "R87") (pin "2") (pinfunction "2_2") (pintype "passive"))
      (node (ref "R88") (pin "1") (pinfunction "1_1") (pintype "passive"))
      (node (ref "R88") (pin "2") (pinfunction "2_2") (pintype "passive"))
      (node (ref "R89") (pin "1") (pinfunction "1_1") (pintype "passive"))
      (node (ref "R89") (pin "2") (pinfunction "2_2") (pintype "passive"))
      (node (ref "R92") (pin "1") (pinfunction "1_1") (pintype "passive"))
      (node (ref "R92") (pin "2") (pinfunction "2_2") (pintype "passive"))
      (node (ref "R93") (pin "1") (pinfunction "1_1") (pintype "passive"))
      (node (ref "R93") (pin "2") (pinfunction "2_2") (pintype "passive"))
      (node (ref "SERVO") (pin "4") (pinfunction "S_4") (pintype "passive"))
      (node (ref "SV1") (pin "10") (pinfunction "10_10") (pintype "passive"))
      (node (ref "SV1") (pin "8") (pinfunction "8_8") (pintype "passive"))
      (node (ref "U$1") (pin "OUT-") (pinfunction "OUT-_OUT-") (pintype "bidirectional"))
      (node (ref "X1") (pin "1") (pinfunction "KL_1") (pintype "passive"))
      (node (ref "X11") (pin "6") (pinfunction "S_6") (pintype "passive"))
    )
    (net (code "25") (name "II_CS1") (class "Default")
      (node (ref "IC4") (pin "3") (pinfunction "AIN2_3") (pintype "input"))
      (node (ref "MMS2") (pin "9") (pinfunction "A2(CS1)_9") (pintype "bidirectional"))
    )
    (net (code "26") (name "II_CS2") (class "Default")
      (node (ref "IC4") (pin "4") (pinfunction "AIN3_4") (pintype "input"))
      (node (ref "MMS2") (pin "10") (pinfunction "A3(CS2)_10") (pintype "bidirectional"))
    )
    (net (code "27") (name "I_CS1") (class "Default")
      (node (ref "IC4") (pin "2") (pinfunction "AIN1_2") (pintype "input"))
      (node (ref "MMS1") (pin "9") (pinfunction "A2(CS1)_9") (pintype "bidirectional"))
    )
    (net (code "28") (name "I_CS2") (class "Default")
      (node (ref "IC4") (pin "1") (pinfunction "AIN0_1") (pintype "input"))
      (node (ref "MMS1") (pin "10") (pinfunction "A3(CS2)_10") (pintype "bidirectional"))
    )
    (net (code "29") (name "MISO") (class "Default")
      (node (ref "IC1") (pin "18") (pinfunction "PB4(MISO/PCINT4)_18") (pintype "bidirectional"))
      (node (ref "SV1") (pin "9") (pinfunction "9_9") (pintype "passive"))
      (node (ref "SW2") (pin "5") (pinfunction "5_5") (pintype "passive"))
    )
    (net (code "30") (name "MOSI") (class "Default")
      (node (ref "IC1") (pin "17") (pinfunction "PB3(MOSI/OC2A/PCINT3)_17") (pintype "bidirectional"))
      (node (ref "SV1") (pin "1") (pinfunction "1_1") (pintype "passive"))
      (node (ref "SW2") (pin "4") (pinfunction "4_4") (pintype "passive"))
    )
    (net (code "31") (name "Net-(C5-Pad2)") (class "Default")
      (node (ref "C5") (pin "2") (pinfunction "2_2") (pintype "passive"))
      (node (ref "R21") (pin "1") (pinfunction "1_1") (pintype "passive"))
      (node (ref "R22") (pin "2") (pinfunction "2_2") (pintype "passive"))
    )
    (net (code "32") (name "Net-(C6-Pad2)") (class "Default")
      (node (ref "C6") (pin "2") (pinfunction "2_2") (pintype "passive"))
      (node (ref "R25") (pin "1") (pinfunction "1_1") (pintype "passive"))
      (node (ref "R26") (pin "2") (pinfunction "2_2") (pintype "passive"))
    )
    (net (code "33") (name "Net-(C9-Pad2)") (class "Default")
      (node (ref "C9") (pin "2") (pinfunction "2_2") (pintype "passive"))
      (node (ref "R17") (pin "1") (pinfunction "1_1") (pintype "passive"))
      (node (ref "R18") (pin "2") (pinfunction "2_2") (pintype "passive"))
    )
    (net (code "34") (name "Net-(ENKODER_AA-S)") (class "Default")
      (node (ref "C17") (pin "1") (pinfunction "1_1") (pintype "passive"))
      (node (ref "ENKODER_A") (pin "1") (pinfunction "S_1") (pintype "passive"))
      (node (ref "IC6") (pin "7") (pinfunction "+IN_7") (pintype "input"))
      (node (ref "R110") (pin "1") (pinfunction "1_1") (pintype "passive"))
    )
    (net (code "35") (name "Net-(ENKODER_AB-S)") (class "Default")
      (node (ref "C18") (pin "1") (pinfunction "1_1") (pintype "passive"))
      (node (ref "ENKODER_A") (pin "2") (pinfunction "S_2") (pintype "passive"))
      (node (ref "IC6") (pin "5") (pinfunction "+IN_5") (pintype "input"))
      (node (ref "R111") (pin "1") (pinfunction "1_1") (pintype "passive"))
    )
    (net (code "36") (name "Net-(ENKODER_BA-S)") (class "Default")
      (node (ref "C15") (pin "1") (pinfunction "1_1") (pintype "passive"))
      (node (ref "ENKODER_B") (pin "1") (pinfunction "S_1") (pintype "passive"))
      (node (ref "IC6") (pin "11") (pinfunction "+IN_11") (pintype "input"))
      (node (ref "R117") (pin "1") (pinfunction "1_1") (pintype "passive"))
    )
    (net (code "37") (name "Net-(ENKODER_BB-S)") (class "Default")
      (node (ref "C16") (pin "1") (pinfunction "1_1") (pintype "passive"))
      (node (ref "ENKODER_B") (pin "2") (pinfunction "S_2") (pintype "passive"))
      (node (ref "IC6") (pin "9") (pinfunction "+IN_9") (pintype "input"))
      (node (ref "R109") (pin "1") (pinfunction "1_1") (pintype "passive"))
    )
    (net (code "38") (name "Net-(ENKODER_CC-S)") (class "Default")
      (node (ref "C20") (pin "1") (pinfunction "1_1") (pintype "passive"))
      (node (ref "ENKODER_C") (pin "3") (pinfunction "S_3") (pintype "passive"))
      (node (ref "IC8") (pin "7") (pinfunction "+IN_7") (pintype "input"))
      (node (ref "R113") (pin "1") (pinfunction "1_1") (pintype "passive"))
    )
    (net (code "39") (name "Net-(ENKODER_CD-S)") (class "Default")
      (node (ref "C19") (pin "1") (pinfunction "1_1") (pintype "passive"))
      (node (ref "ENKODER_C") (pin "4") (pinfunction "S_4") (pintype "passive"))
      (node (ref "IC8") (pin "5") (pinfunction "+IN_5") (pintype "input"))
      (node (ref "R112") (pin "1") (pinfunction "1_1") (pintype "passive"))
    )
    (net (code "40") (name "Net-(ENKODER_DC-S)") (class "Default")
      (node (ref "C22") (pin "1") (pinfunction "1_1") (pintype "passive"))
      (node (ref "ENKODER_D") (pin "3") (pinfunction "S_3") (pintype "passive"))
      (node (ref "IC8") (pin "11") (pinfunction "+IN_11") (pintype "input"))
      (node (ref "R114") (pin "1") (pinfunction "1_1") (pintype "passive"))
    )
    (net (code "41") (name "Net-(ENKODER_DD-S)") (class "Default")
      (node (ref "C21") (pin "1") (pinfunction "1_1") (pintype "passive"))
      (node (ref "ENKODER_D") (pin "4") (pinfunction "S_4") (pintype "passive"))
      (node (ref "IC8") (pin "9") (pinfunction "+IN_9") (pintype "input"))
      (node (ref "R115") (pin "1") (pinfunction "1_1") (pintype "passive"))
    )
    (net (code "42") (name "Net-(GPIO1-GPIO06)") (class "Default")
      (node (ref "GPIO1") (pin "31") (pinfunction "GPIO06_31") (pintype "bidirectional"))
      (node (ref "R14") (pin "1") (pinfunction "1_1") (pintype "passive"))
    )
    (net (code "43") (name "Net-(GPIO1-GPIO08(SPI_CE0_N))") (class "Default")
      (node (ref "GPIO1") (pin "24") (pinfunction "GPIO08(SPI_CE0_N)_24") (pintype "bidirectional"))
      (node (ref "R29") (pin "1") (pinfunction "1_1") (pintype "passive"))
    )
    (net (code "44") (name "Net-(GPIO1-GPIO09(SPI_MISO))") (class "Default")
      (node (ref "GPIO1") (pin "21") (pinfunction "GPIO09(SPI_MISO)_21") (pintype "bidirectional"))
      (node (ref "R8") (pin "1") (pinfunction "1_1") (pintype "passive"))
      (node (ref "TX7") (pin "3") (pinfunction "S_3") (pintype "passive"))
    )
    (net (code "45") (name "Net-(GPIO1-GPIO10(SPI_MOSI))") (class "Default")
      (node (ref "GPIO1") (pin "19") (pinfunction "GPIO10(SPI_MOSI)_19") (pintype "bidirectional"))
      (node (ref "R6") (pin "1") (pinfunction "1_1") (pintype "passive"))
      (node (ref "TX6") (pin "3") (pinfunction "S_3") (pintype "passive"))
    )
    (net (code "46") (name "Net-(GPIO1-GPIO11(SPI_CLK))") (class "Default")
      (node (ref "GPIO1") (pin "23") (pinfunction "GPIO11(SPI_CLK)_23") (pintype "bidirectional"))
      (node (ref "R10") (pin "1") (pinfunction "1_1") (pintype "passive"))
      (node (ref "TX8") (pin "3") (pinfunction "S_3") (pintype "passive"))
    )
    (net (code "47") (name "Net-(GPIO1-GPIO13)") (class "Default")
      (node (ref "GPIO1") (pin "33") (pinfunction "GPIO13_33") (pintype "bidirectional"))
      (node (ref "R67") (pin "1") (pinfunction "1_1") (pintype "passive"))
    )
    (net (code "48") (name "Net-(GPIO1-GPIO14(TXD0))") (class "Default")
      (node (ref "GPIO1") (pin "8") (pinfunction "GPIO14(TXD0)_8") (pintype "bidirectional"))
      (node (ref "R2") (pin "1") (pinfunction "1_1") (pintype "passive"))
      (node (ref "TX") (pin "3") (pinfunction "S_3") (pintype "passive"))
    )
    (net (code "49") (name "Net-(GPIO1-GPIO15(RXD0))") (class "Default")
      (node (ref "GPIO1") (pin "10") (pinfunction "GPIO15(RXD0)_10") (pintype "bidirectional"))
      (node (ref "R4") (pin "1") (pinfunction "1_1") (pintype "passive"))
      (node (ref "TX5") (pin "3") (pinfunction "S_3") (pintype "passive"))
    )
    (net (code "50") (name "Net-(GPIO1-GPIO19)") (class "Default")
      (node (ref "GPIO1") (pin "35") (pinfunction "GPIO19_35") (pintype "bidirectional"))
      (node (ref "R69") (pin "1") (pinfunction "1_1") (pintype "passive"))
    )
    (net (code "51") (name "Net-(GPIO1-GPIO21)") (class "Default")
      (node (ref "GPIO1") (pin "40") (pinfunction "GPIO21_40") (pintype "bidirectional"))
      (node (ref "LED3") (pin "K") (pinfunction "C_K") (pintype "passive"))
    )
    (net (code "52") (name "Net-(GPIO1-GPIO23(GPIO_GEN4))") (class "Default")
      (node (ref "GPIO1") (pin "16") (pinfunction "GPIO23(GPIO_GEN4)_16") (pintype "bidirectional"))
      (node (ref "R76") (pin "1") (pinfunction "1_1") (pintype "passive"))
    )
    (net (code "53") (name "Net-(GPIO1-GPIO24(GPIO_GEN5))") (class "Default")
      (node (ref "GPIO1") (pin "18") (pinfunction "GPIO24(GPIO_GEN5)_18") (pintype "bidirectional"))
      (node (ref "R75") (pin "1") (pinfunction "1_1") (pintype "passive"))
    )
    (net (code "54") (name "Net-(GPIO1-GPIO25(GPIO_GEN6))") (class "Default")
      (node (ref "GPIO1") (pin "22") (pinfunction "GPIO25(GPIO_GEN6)_22") (pintype "bidirectional"))
      (node (ref "R30") (pin "1") (pinfunction "1_1") (pintype "passive"))
    )
    (net (code "55") (name "Net-(GPIO1-GPIO26)") (class "Default")
      (node (ref "GPIO1") (pin "37") (pinfunction "GPIO26_37") (pintype "bidirectional"))
      (node (ref "R71") (pin "1") (pinfunction "1_1") (pintype "passive"))
    )
    (net (code "56") (name "Net-(IC1-AREF)") (class "Default")
      (node (ref "C14") (pin "1") (pinfunction "1_1") (pintype "passive"))
      (node (ref "IC1") (pin "21") (pinfunction "AREF_21") (pintype "passive"))
    )
    (net (code "57") (name "Net-(IC1-PB0(ICP1{slash}CLKO{slash}PCINT0))") (class "Default")
      (node (ref "IC1") (pin "14") (pinfunction "PB0(ICP1/CLKO/PCINT0)_14") (pintype "bidirectional"))
      (node (ref "LED1") (pin "K") (pinfunction "C_K") (pintype "passive"))
    )
    (net (code "58") (name "Net-(IC1-PB1(OC1A{slash}PCINT1))") (class "Default")
      (node (ref "IC1") (pin "15") (pinfunction "PB1(OC1A/PCINT1)_15") (pintype "bidirectional"))
      (node (ref "MMS2") (pin "15") (pinfunction "D5(PWM1)_15") (pintype "bidirectional"))
    )
    (net (code "59") (name "Net-(IC1-PB2(SS{slash}OC1B{slash}PCINT2))") (class "Default")
      (node (ref "IC1") (pin "16") (pinfunction "PB2(SS/OC1B/PCINT2)_16") (pintype "bidirectional"))
      (node (ref "MMS2") (pin "14") (pinfunction "D6(PWM2)_14") (pintype "bidirectional"))
    )
    (net (code "60") (name "Net-(IC1-PB6(XTAL1{slash}TOSC1{slash}PCINT6))") (class "Default")
      (node (ref "C3") (pin "2") (pinfunction "2_2") (pintype "passive"))
      (node (ref "IC1") (pin "9") (pinfunction "PB6(XTAL1/TOSC1/PCINT6)_9") (pintype "bidirectional"))
      (node (ref "Q1") (pin "2") (pinfunction "2_2") (pintype "passive"))
    )
    (net (code "61") (name "Net-(IC1-PB7(XTAL2{slash}TOSC2{slash}PCINT7))") (class "Default")
      (node (ref "C4") (pin "2") (pinfunction "2_2") (pintype "passive"))
      (node (ref "IC1") (pin "10") (pinfunction "PB7(XTAL2/TOSC2/PCINT7)_10") (pintype "bidirectional"))
      (node (ref "Q1") (pin "1") (pinfunction "1_1") (pintype "passive"))
    )
    (net (code "62") (name "Net-(IC1-PD0(RXD{slash}PCINT16))") (class "Default")
      (node (ref "IC1") (pin "2") (pinfunction "PD0(RXD/PCINT16)_2") (pintype "bidirectional"))
      (node (ref "UART_A") (pin "1") (pinfunction "S_1") (pintype "passive"))
    )
    (net (code "63") (name "Net-(IC1-PD1(TXD{slash}PCINT17))") (class "Default")
      (node (ref "IC1") (pin "3") (pinfunction "PD1(TXD/PCINT17)_3") (pintype "bidirectional"))
      (node (ref "UART_A") (pin "2") (pinfunction "S_2") (pintype "passive"))
    )
    (net (code "64") (name "Net-(IC1-PD5(T1{slash}OC0B{slash}PCINT21))") (class "Default")
      (node (ref "IC1") (pin "11") (pinfunction "PD5(T1/OC0B/PCINT21)_11") (pintype "bidirectional"))
      (node (ref "R12") (pin "1") (pinfunction "1_1") (pintype "passive"))
    )
    (net (code "65") (name "Net-(IC1-PD6(AIN0{slash}OC0A{slash}PCINT22))") (class "Default")
      (node (ref "IC1") (pin "12") (pinfunction "PD6(AIN0/OC0A/PCINT22)_12") (pintype "bidirectional"))
      (node (ref "R13") (pin "1") (pinfunction "1_1") (pintype "passive"))
    )
    (net (code "66") (name "Net-(IC2-AIN0)") (class "Default")
      (node (ref "D1") (pin "A") (pinfunction "A_A") (pintype "passive"))
      (node (ref "D2") (pin "C") (pinfunction "C_C") (pintype "passive"))
      (node (ref "IC2") (pin "1") (pinfunction "AIN0_1") (pintype "input"))
      (node (ref "R17") (pin "2") (pinfunction "2_2") (pintype "passive"))
    )
    (net (code "67") (name "Net-(IC2-AIN1)") (class "Default")
      (node (ref "D3") (pin "A") (pinfunction "A_A") (pintype "passive"))
      (node (ref "D4") (pin "C") (pinfunction "C_C") (pintype "passive"))
      (node (ref "IC2") (pin "2") (pinfunction "AIN1_2") (pintype "input"))
      (node (ref "R21") (pin "2") (pinfunction "2_2") (pintype "passive"))
    )
    (net (code "68") (name "Net-(IC2-AIN2)") (class "Default")
      (node (ref "D5") (pin "A") (pinfunction "A_A") (pintype "passive"))
      (node (ref "D6") (pin "C") (pinfunction "C_C") (pintype "passive"))
      (node (ref "IC2") (pin "3") (pinfunction "AIN2_3") (pintype "input"))
      (node (ref "R25") (pin "2") (pinfunction "2_2") (pintype "passive"))
    )
    (net (code "69") (name "Net-(IC2-VREF)") (class "Default")
      (node (ref "C29") (pin "+") (pinfunction "+_+") (pintype "passive"))
      (node (ref "C8") (pin "2") (pinfunction "2_2") (pintype "passive"))
      (node (ref "D7") (pin "C") (pinfunction "C_C") (pintype "passive"))
      (node (ref "IC2") (pin "14") (pinfunction "VREF_14") (pintype "input"))
    )
    (net (code "70") (name "Net-(IC3A-+IN)") (class "Default")
      (node (ref "IC3") (pin "3") (pinfunction "+IN_3") (pintype "input"))
      (node (ref "R27") (pin "2") (pinfunction "2_2") (pintype "passive"))
      (node (ref "R28") (pin "1") (pinfunction "1_1") (pintype "passive"))
    )
    (net (code "71") (name "Net-(IC3A--IN)") (class "Default")
      (node (ref "IC3") (pin "1") (pinfunction "OUT_1") (pintype "output"))
      (node (ref "IC3") (pin "2") (pinfunction "-IN_2") (pintype "input"))
      (node (ref "R26") (pin "1") (pinfunction "1_1") (pintype "passive"))
    )
    (net (code "72") (name "Net-(IC3B-+IN)") (class "Default")
      (node (ref "IC3") (pin "5") (pinfunction "+IN_5") (pintype "input"))
      (node (ref "R23") (pin "2") (pinfunction "2_2") (pintype "passive"))
      (node (ref "R24") (pin "1") (pinfunction "1_1") (pintype "passive"))
    )
    (net (code "73") (name "Net-(IC3B--IN)") (class "Default")
      (node (ref "IC3") (pin "6") (pinfunction "-IN_6") (pintype "input"))
      (node (ref "IC3") (pin "7") (pinfunction "OUT_7") (pintype "output"))
      (node (ref "R22") (pin "1") (pinfunction "1_1") (pintype "passive"))
    )
    (net (code "74") (name "Net-(IC3C--IN)") (class "Default")
      (node (ref "IC3") (pin "8") (pinfunction "OUT_8") (pintype "output"))
      (node (ref "IC3") (pin "9") (pinfunction "-IN_9") (pintype "input"))
    )
    (net (code "75") (name "Net-(IC3D-+IN)") (class "Default")
      (node (ref "IC3") (pin "12") (pinfunction "+IN_12") (pintype "input"))
      (node (ref "R19") (pin "2") (pinfunction "2_2") (pintype "passive"))
      (node (ref "R20") (pin "1") (pinfunction "1_1") (pintype "passive"))
    )
    (net (code "76") (name "Net-(IC3D--IN)") (class "Default")
      (node (ref "IC3") (pin "13") (pinfunction "-IN_13") (pintype "input"))
      (node (ref "IC3") (pin "14") (pinfunction "OUT_14") (pintype "output"))
      (node (ref "R18") (pin "1") (pinfunction "1_1") (pintype "passive"))
    )
    (net (code "77") (name "Net-(IC4-SCL)") (class "Default")
      (node (ref "IC4") (pin "10") (pinfunction "SCL_10") (pintype "input"))
      (node (ref "R31") (pin "2") (pinfunction "2_2") (pintype "passive"))
    )
    (net (code "78") (name "Net-(IC4-SDA)") (class "Default")
      (node (ref "IC4") (pin "9") (pinfunction "SDA_9") (pintype "bidirectional"))
      (node (ref "R36") (pin "2") (pinfunction "2_2") (pintype "passive"))
    )
    (net (code "79") (name "Net-(IC4-VREF)") (class "Default")
      (node (ref "C11") (pin "2") (pinfunction "2_2") (pintype "passive"))
      (node (ref "IC4") (pin "14") (pinfunction "VREF_14") (pintype "input"))
    )
    (net (code "80") (name "Net-(IC6A--IN)") (class "Default")
      (node (ref "IC6") (pin "4") (pinfunction "-IN_4") (pintype "input"))
      (node (ref "R52") (pin "1") (pinfunction "1_1") (pintype "passive"))
      (node (ref "R53") (pin "2") (pinfunction "2_2") (pintype "passive"))
    )
    (net (code "81") (name "Net-(IC6B--IN)") (class "Default")
      (node (ref "IC6") (pin "6") (pinfunction "-IN_6") (pintype "input"))
      (node (ref "R49") (pin "1") (pinfunction "1_1") (pintype "passive"))
      (node (ref "R50") (pin "2") (pinfunction "2_2") (pintype "passive"))
    )
    (net (code "82") (name "Net-(IC6C--IN)") (class "Default")
      (node (ref "IC6") (pin "8") (pinfunction "-IN_8") (pintype "input"))
      (node (ref "R46") (pin "1") (pinfunction "1_1") (pintype "passive"))
      (node (ref "R47") (pin "2") (pinfunction "2_2") (pintype "passive"))
    )
    (net (code "83") (name "Net-(IC6D--IN)") (class "Default")
      (node (ref "IC6") (pin "10") (pinfunction "-IN_10") (pintype "input"))
      (node (ref "R43") (pin "1") (pinfunction "1_1") (pintype "passive"))
      (node (ref "R44") (pin "2") (pinfunction "2_2") (pintype "passive"))
    )
    (net (code "84") (name "Net-(IC8A--IN)") (class "Default")
      (node (ref "IC8") (pin "4") (pinfunction "-IN_4") (pintype "input"))
      (node (ref "R55") (pin "1") (pinfunction "1_1") (pintype "passive"))
      (node (ref "R56") (pin "2") (pinfunction "2_2") (pintype "passive"))
    )
    (net (code "85") (name "Net-(IC8B--IN)") (class "Default")
      (node (ref "IC8") (pin "6") (pinfunction "-IN_6") (pintype "input"))
      (node (ref "R58") (pin "1") (pinfunction "1_1") (pintype "passive"))
      (node (ref "R59") (pin "2") (pinfunction "2_2") (pintype "passive"))
    )
    (net (code "86") (name "Net-(IC8C--IN)") (class "Default")
      (node (ref "IC8") (pin "8") (pinfunction "-IN_8") (pintype "input"))
      (node (ref "R61") (pin "1") (pinfunction "1_1") (pintype "passive"))
      (node (ref "R62") (pin "2") (pinfunction "2_2") (pintype "passive"))
    )
    (net (code "87") (name "Net-(IC8D--IN)") (class "Default")
      (node (ref "IC8") (pin "10") (pinfunction "-IN_10") (pintype "input"))
      (node (ref "R64") (pin "1") (pinfunction "1_1") (pintype "passive"))
      (node (ref "R65") (pin "2") (pinfunction "2_2") (pintype "passive"))
    )
    (net (code "88") (name "Net-(LED1-PadA)") (class "Default")
      (node (ref "LED1") (pin "A") (pinfunction "A_A") (pintype "passive"))
      (node (ref "R102") (pin "1") (pinfunction "1_1") (pintype "passive"))
    )
    (net (code "89") (name "Net-(LED3-PadA)") (class "Default")
      (node (ref "LED3") (pin "A") (pinfunction "A_A") (pintype "passive"))
      (node (ref "R73") (pin "1") (pinfunction "1_1") (pintype "passive"))
    )
    (net (code "90") (name "Net-(MMS1-D5(PWM1))") (class "Default")
      (node (ref "MMS1") (pin "15") (pinfunction "D5(PWM1)_15") (pintype "bidirectional"))
      (node (ref "R13") (pin "2") (pinfunction "2_2") (pintype "passive"))
    )
    (net (code "91") (name "Net-(MMS1-D6(PWM2))") (class "Default")
      (node (ref "MMS1") (pin "14") (pinfunction "D6(PWM2)_14") (pintype "bidirectional"))
      (node (ref "R12") (pin "2") (pinfunction "2_2") (pintype "passive"))
    )
    (net (code "92") (name "Net-(R101-Pad1)") (class "Default")
      (node (ref "R101") (pin "1") (pinfunction "1_1") (pintype "passive"))
      (node (ref "SV1") (pin "5") (pinfunction "5_5") (pintype "passive"))
    )
    (net (code "93") (name "Net-(SERVOA-S)") (class "Default")
      (node (ref "R76") (pin "2") (pinfunction "2_2") (pintype "passive"))
      (node (ref "SERVO") (pin "1") (pinfunction "S_1") (pintype "passive"))
    )
    (net (code "94") (name "Net-(SERVOB-S)") (class "Default")
      (node (ref "R75") (pin "2") (pinfunction "2_2") (pintype "passive"))
      (node (ref "SERVO") (pin "2") (pinfunction "S_2") (pintype "passive"))
    )
    (net (code "95") (name "Net-(TX-D)") (class "Default")
      (node (ref "R3") (pin "1") (pinfunction "1_1") (pintype "passive"))
      (node (ref "TX") (pin "1") (pinfunction "D_1") (pintype "passive"))
      (node (ref "UART_R") (pin "1") (pinfunction "S_1") (pintype "passive"))
    )
    (net (code "96") (name "Net-(TX1-D)") (class "Default")
      (node (ref "R33") (pin "1") (pinfunction "1_1") (pintype "passive"))
      (node (ref "R36") (pin "1") (pinfunction "1_1") (pintype "passive"))
      (node (ref "TX1") (pin "1") (pinfunction "D_1") (pintype "passive"))
    )
    (net (code "97") (name "Net-(TX2-D)") (class "Default")
      (node (ref "R31") (pin "1") (pinfunction "1_1") (pintype "passive"))
      (node (ref "R35") (pin "1") (pinfunction "1_1") (pintype "passive"))
      (node (ref "TX2") (pin "1") (pinfunction "D_1") (pintype "passive"))
    )
    (net (code "98") (name "Net-(TX3-D)") (class "Default")
      (node (ref "R40") (pin "1") (pinfunction "1_1") (pintype "passive"))
      (node (ref "TX3") (pin "1") (pinfunction "D_1") (pintype "passive"))
      (node (ref "X11") (pin "3") (pinfunction "S_3") (pintype "passive"))
    )
    (net (code "99") (name "Net-(TX4-D)") (class "Default")
      (node (ref "R42") (pin "1") (pinfunction "1_1") (pintype "passive"))
      (node (ref "TX4") (pin "1") (pinfunction "D_1") (pintype "passive"))
      (node (ref "X11") (pin "4") (pinfunction "S_4") (pintype "passive"))
    )
    (net (code "100") (name "Net-(TX5-D)") (class "Default")
      (node (ref "R5") (pin "1") (pinfunction "1_1") (pintype "passive"))
      (node (ref "TX5") (pin "1") (pinfunction "D_1") (pintype "passive"))
      (node (ref "UART_R") (pin "2") (pinfunction "S_2") (pintype "passive"))
    )
    (net (code "101") (name "Net-(TX6-D)") (class "Default")
      (node (ref "R7") (pin "1") (pinfunction "1_1") (pintype "passive"))
      (node (ref "SW2") (pin "3") (pinfunction "3_3") (pintype "passive"))
      (node (ref "TX6") (pin "1") (pinfunction "D_1") (pintype "passive"))
    )
    (net (code "102") (name "Net-(TX7-D)") (class "Default")
      (node (ref "R9") (pin "1") (pinfunction "1_1") (pintype "passive"))
      (node (ref "SW2") (pin "2") (pinfunction "2_2") (pintype "passive"))
      (node (ref "TX7") (pin "1") (pinfunction "D_1") (pintype "passive"))
    )
    (net (code "103") (name "Net-(TX8-D)") (class "Default")
      (node (ref "R11") (pin "1") (pinfunction "1_1") (pintype "passive"))
      (node (ref "SW2") (pin "1") (pinfunction "1_1") (pintype "passive"))
      (node (ref "TX8") (pin "1") (pinfunction "D_1") (pintype "passive"))
    )
    (net (code "104") (name "Net-(X12A-KL)") (class "Default")
      (node (ref "U$1") (pin "IN+") (pinfunction "IN+_IN+") (pintype "bidirectional"))
      (node (ref "X12") (pin "1") (pinfunction "KL_1") (pintype "passive"))
    )
    (net (code "105") (name "Net-(X12B-KL)") (class "Default")
      (node (ref "U$1") (pin "IN-") (pinfunction "IN-_IN-") (pintype "bidirectional"))
      (node (ref "X12") (pin "2") (pinfunction "KL_2") (pintype "passive"))
    )
    (net (code "106") (name "RST") (class "Default")
      (node (ref "IC1") (pin "1") (pinfunction "PC6(/RESET/PCINT14)_1") (pintype "bidirectional"))
      (node (ref "R1") (pin "1") (pinfunction "1_1") (pintype "passive"))
      (node (ref "R101") (pin "2") (pinfunction "2_2") (pintype "passive"))
    )
    (net (code "107") (name "SCK") (class "Default")
      (node (ref "IC1") (pin "19") (pinfunction "PB5(SCK/PCINT5)_19") (pintype "bidirectional"))
      (node (ref "SV1") (pin "7") (pinfunction "7_7") (pintype "passive"))
      (node (ref "SW2") (pin "6") (pinfunction "6_6") (pintype "passive"))
    )
    (net (code "108") (name "SCL") (class "Default")
      (node (ref "GPIO1") (pin "5") (pinfunction "GPIO3(SCL1)_5") (pintype "bidirectional"))
      (node (ref "IC2") (pin "10") (pinfunction "SCL_10") (pintype "input"))
      (node (ref "R15") (pin "1") (pinfunction "1_1") (pintype "passive"))
      (node (ref "R34") (pin "1") (pinfunction "1_1") (pintype "passive"))
      (node (ref "TX2") (pin "3") (pinfunction "S_3") (pintype "passive"))
    )
    (net (code "109") (name "SDA") (class "Default")
      (node (ref "GPIO1") (pin "3") (pinfunction "GPIO2(SDA1)_3") (pintype "bidirectional"))
      (node (ref "IC2") (pin "9") (pinfunction "SDA_9") (pintype "bidirectional"))
      (node (ref "R16") (pin "1") (pinfunction "1_1") (pintype "passive"))
      (node (ref "R32") (pin "1") (pinfunction "1_1") (pintype "passive"))
      (node (ref "TX1") (pin "3") (pinfunction "S_3") (pintype "passive"))
    )
    (net (code "110") (name "TRIG_1") (class "Default")
      (node (ref "R30") (pin "2") (pinfunction "2_2") (pintype "passive"))
      (node (ref "X11") (pin "1") (pinfunction "S_1") (pintype "passive"))
    )
    (net (code "111") (name "TRIG_2") (class "Default")
      (node (ref "R29") (pin "2") (pinfunction "2_2") (pintype "passive"))
      (node (ref "X11") (pin "2") (pinfunction "S_2") (pintype "passive"))
    )
    (net (code "112") (name "VCC") (class "Default")
      (node (ref "C1") (pin "+") (pinfunction "+_+") (pintype "passive"))
      (node (ref "C10") (pin "2") (pinfunction "2_2") (pintype "passive"))
      (node (ref "C12") (pin "1") (pinfunction "1_1") (pintype "passive"))
      (node (ref "C13") (pin "1") (pinfunction "1_1") (pintype "passive"))
      (node (ref "C2") (pin "1") (pinfunction "1_1") (pintype "passive"))
      (node (ref "C23") (pin "1") (pinfunction "1_1") (pintype "passive"))
      (node (ref "C24") (pin "1") (pinfunction "1_1") (pintype "passive"))
      (node (ref "C26") (pin "1") (pinfunction "1_1") (pintype "passive"))
      (node (ref "ENKODER_A") (pin "4") (pinfunction "S_4") (pintype "passive"))
      (node (ref "ENKODER_B") (pin "4") (pinfunction "S_4") (pintype "passive"))
      (node (ref "ENKODER_C") (pin "1") (pinfunction "S_1") (pintype "passive"))
      (node (ref "ENKODER_D") (pin "1") (pinfunction "S_1") (pintype "passive"))
      (node (ref "IC1") (pin "20") (pinfunction "AVCC_20") (pintype "passive"))
      (node (ref "IC1") (pin "7") (pinfunction "VCC_7") (pintype "power_in"))
      (node (ref "IC4") (pin "16") (pinfunction "VDD_16") (pintype "power_in"))
      (node (ref "IC4") (pin "5") (pinfunction "A0_5") (pintype "input"))
      (node (ref "IC6") (pin "3") (pinfunction "V+_3") (pintype "power_in"))
      (node (ref "IC8") (pin "3") (pinfunction "V+_3") (pintype "power_in"))
      (node (ref "J1") (pin "2") (pinfunction "2_2") (pintype "passive"))
      (node (ref "MMS1") (pin "3") (pinfunction "5V_3") (pintype "bidirectional"))
      (node (ref "MMS2") (pin "3") (pinfunction "5V_3") (pintype "bidirectional"))
      (node (ref "R1") (pin "2") (pinfunction "2_2") (pintype "passive"))
      (node (ref "R102") (pin "2") (pinfunction "2_2") (pintype "passive"))
      (node (ref "R109") (pin "2") (pinfunction "2_2") (pintype "passive"))
      (node (ref "R11") (pin "2") (pinfunction "2_2") (pintype "passive"))
      (node (ref "R110") (pin "2") (pinfunction "2_2") (pintype "passive"))
      (node (ref "R111") (pin "2") (pinfunction "2_2") (pintype "passive"))
      (node (ref "R112") (pin "2") (pinfunction "2_2") (pintype "passive"))
      (node (ref "R113") (pin "2") (pinfunction "2_2") (pintype "passive"))
      (node (ref "R114") (pin "2") (pinfunction "2_2") (pintype "passive"))
      (node (ref "R115") (pin "2") (pinfunction "2_2") (pintype "passive"))
      (node (ref "R117") (pin "2") (pinfunction "2_2") (pintype "passive"))
      (node (ref "R3") (pin "2") (pinfunction "2_2") (pintype "passive"))
      (node (ref "R33") (pin "2") (pinfunction "2_2") (pintype "passive"))
      (node (ref "R35") (pin "2") (pinfunction "2_2") (pintype "passive"))
      (node (ref "R40") (pin "2") (pinfunction "2_2") (pintype "passive"))
      (node (ref "R42") (pin "2") (pinfunction "2_2") (pintype "passive"))
      (node (ref "R43") (pin "2") (pinfunction "2_2") (pintype "passive"))
      (node (ref "R45") (pin "2") (pinfunction "2_2") (pintype "passive"))
      (node (ref "R46") (pin "2") (pinfunction "2_2") (pintype "passive"))
      (node (ref "R48") (pin "2") (pinfunction "2_2") (pintype "passive"))
      (node (ref "R49") (pin "2") (pinfunction "2_2") (pintype "passive"))
      (node (ref "R5") (pin "2") (pinfunction "2_2") (pintype "passive"))
      (node (ref "R51") (pin "2") (pinfunction "2_2") (pintype "passive"))
      (node (ref "R52") (pin "2") (pinfunction "2_2") (pintype "passive"))
      (node (ref "R54") (pin "2") (pinfunction "2_2") (pintype "passive"))
      (node (ref "R55") (pin "2") (pinfunction "2_2") (pintype "passive"))
      (node (ref "R57") (pin "2") (pinfunction "2_2") (pintype "passive"))
      (node (ref "R58") (pin "2") (pinfunction "2_2") (pintype "passive"))
      (node (ref "R60") (pin "2") (pinfunction "2_2") (pintype "passive"))
      (node (ref "R61") (pin "2") (pinfunction "2_2") (pintype "passive"))
      (node (ref "R63") (pin "2") (pinfunction "2_2") (pintype "passive"))
      (node (ref "R64") (pin "2") (pinfunction "2_2") (pintype "passive"))
      (node (ref "R66") (pin "2") (pinfunction "2_2") (pintype "passive"))
      (node (ref "R7") (pin "2") (pinfunction "2_2") (pintype "passive"))
      (node (ref "R70") (pin "1") (pinfunction "1_1") (pintype "passive"))
      (node (ref "R70") (pin "2") (pinfunction "2_2") (pintype "passive"))
      (node (ref "R79") (pin "1") (pinfunction "1_1") (pintype "passive"))
      (node (ref "R79") (pin "2") (pinfunction "2_2") (pintype "passive"))
      (node (ref "R80") (pin "1") (pinfunction "1_1") (pintype "passive"))
      (node (ref "R80") (pin "2") (pinfunction "2_2") (pintype "passive"))
      (node (ref "R9") (pin "2") (pinfunction "2_2") (pintype "passive"))
      (node (ref "R90") (pin "1") (pinfunction "1_1") (pintype "passive"))
      (node (ref "R90") (pin "2") (pinfunction "2_2") (pintype "passive"))
      (node (ref "R91") (pin "1") (pinfunction "1_1") (pintype "passive"))
      (node (ref "R91") (pin "2") (pinfunction "2_2") (pintype "passive"))
      (node (ref "R94") (pin "1") (pinfunction "1_1") (pintype "passive"))
      (node (ref "R94") (pin "2") (pinfunction "2_2") (pintype "passive"))
      (node (ref "R95") (pin "1") (pinfunction "1_1") (pintype "passive"))
      (node (ref "R95") (pin "2") (pinfunction "2_2") (pintype "passive"))
      (node (ref "R96") (pin "1") (pinfunction "1_1") (pintype "passive"))
      (node (ref "R96") (pin "2") (pinfunction "2_2") (pintype "passive"))
      (node (ref "R97") (pin "1") (pinfunction "1_1") (pintype "passive"))
      (node (ref "R97") (pin "2") (pinfunction "2_2") (pintype "passive"))
      (node (ref "R98") (pin "1") (pinfunction "1_1") (pintype "passive"))
      (node (ref "R98") (pin "2") (pinfunction "2_2") (pintype "passive"))
      (node (ref "R99") (pin "1") (pinfunction "1_1") (pintype "passive"))
      (node (ref "R99") (pin "2") (pinfunction "2_2") (pintype "passive"))
      (node (ref "SERVO") (pin "3") (pinfunction "S_3") (pintype "passive"))
      (node (ref "U$1") (pin "OUT+") (pinfunction "OUT+_OUT+") (pintype "bidirectional"))
      (node (ref "X1") (pin "2") (pinfunction "KL_2") (pintype "passive"))
      (node (ref "X11") (pin "5") (pinfunction "S_5") (pintype "passive"))
    )
    (net (code "113") (name "unconnected-(GPIO1-5V-Pad2)") (class "Default")
      (node (ref "GPIO1") (pin "2") (pinfunction "5V_2") (pintype "bidirectional"))
    )
    (net (code "114") (name "unconnected-(GPIO1-5V-Pad4)") (class "Default")
      (node (ref "GPIO1") (pin "4") (pinfunction "5V_4") (pintype "bidirectional"))
    )
    (net (code "115") (name "unconnected-(GPIO1-GPIO05-Pad29)") (class "Default")
      (node (ref "GPIO1") (pin "29") (pinfunction "GPIO05_29") (pintype "bidirectional"))
    )
    (net (code "116") (name "unconnected-(GPIO1-GPIO12-Pad32)") (class "Default")
      (node (ref "GPIO1") (pin "32") (pinfunction "GPIO12_32") (pintype "bidirectional"))
    )
    (net (code "117") (name "unconnected-(GPIO1-GPIO16-Pad36)") (class "Default")
      (node (ref "GPIO1") (pin "36") (pinfunction "GPIO16_36") (pintype "bidirectional"))
    )
    (net (code "118") (name "unconnected-(GPIO1-GPIO18(GPIO_GEN1)-Pad12)") (class "Default")
      (node (ref "GPIO1") (pin "12") (pinfunction "GPIO18(GPIO_GEN1)_12") (pintype "bidirectional"))
    )
    (net (code "119") (name "unconnected-(GPIO1-GPIO20-Pad38)") (class "Default")
      (node (ref "GPIO1") (pin "38") (pinfunction "GPIO20_38") (pintype "bidirectional"))
    )
    (net (code "120") (name "unconnected-(GPIO1-ID_SD(I2C_ID_EEPROM)-Pad27)") (class "Default")
      (node (ref "GPIO1") (pin "27") (pinfunction "ID_SD(I2C_ID_EEPROM)_27") (pintype "bidirectional"))
    )
    (net (code "121") (name "unconnected-(IC1-PC0(ADC0{slash}PCINT8)-Pad23)") (class "Default")
      (node (ref "IC1") (pin "23") (pinfunction "PC0(ADC0/PCINT8)_23") (pintype "bidirectional"))
    )
    (net (code "122") (name "unconnected-(IC1-PD7(AIN1{slash}PCINT23)-Pad13)") (class "Default")
      (node (ref "IC1") (pin "13") (pinfunction "PD7(AIN1/PCINT23)_13") (pintype "bidirectional"))
    )
    (net (code "123") (name "unconnected-(IC2-AOUT-Pad15)") (class "Default")
      (node (ref "IC2") (pin "15") (pinfunction "AOUT_15") (pintype "output"))
    )
    (net (code "124") (name "unconnected-(IC2-OSC-Pad11)") (class "Default")
      (node (ref "IC2") (pin "11") (pinfunction "OSC_11") (pintype "input"))
    )
    (net (code "125") (name "unconnected-(IC4-AOUT-Pad15)") (class "Default")
      (node (ref "IC4") (pin "15") (pinfunction "AOUT_15") (pintype "output"))
    )
    (net (code "126") (name "unconnected-(IC4-OSC-Pad11)") (class "Default")
      (node (ref "IC4") (pin "11") (pinfunction "OSC_11") (pintype "input"))
    )
    (net (code "127") (name "unconnected-(MMS1-3.3V-Pad2)") (class "Default")
      (node (ref "MMS1") (pin "2") (pinfunction "3.3V_2") (pintype "bidirectional"))
    )
    (net (code "128") (name "unconnected-(MMS1-A0(EN1)-Pad7)") (class "Default")
      (node (ref "MMS1") (pin "7") (pinfunction "A0(EN1)_7") (pintype "bidirectional"))
    )
    (net (code "129") (name "unconnected-(MMS1-A1(EN2)-Pad8)") (class "Default")
      (node (ref "MMS1") (pin "8") (pinfunction "A1(EN2)_8") (pintype "bidirectional"))
    )
    (net (code "130") (name "unconnected-(MMS1-A4-Pad11)") (class "Default")
      (node (ref "MMS1") (pin "11") (pinfunction "A4_11") (pintype "bidirectional"))
    )
    (net (code "131") (name "unconnected-(MMS1-A5-Pad12)") (class "Default")
      (node (ref "MMS1") (pin "12") (pinfunction "A5_12") (pintype "bidirectional"))
    )
    (net (code "132") (name "unconnected-(MMS1-AREF-Pad21)") (class "Default")
      (node (ref "MMS1") (pin "21") (pinfunction "AREF_21") (pintype "bidirectional"))
    )
    (net (code "133") (name "unconnected-(MMS1-D2-Pad18)") (class "Default")
      (node (ref "MMS1") (pin "18") (pinfunction "D2_18") (pintype "bidirectional"))
    )
    (net (code "134") (name "unconnected-(MMS1-D3-Pad17)") (class "Default")
      (node (ref "MMS1") (pin "17") (pinfunction "D3_17") (pintype "bidirectional"))
    )
    (net (code "135") (name "unconnected-(MMS1-D10-Pad26)") (class "Default")
      (node (ref "MMS1") (pin "26") (pinfunction "D10_26") (pintype "bidirectional"))
    )
    (net (code "136") (name "unconnected-(MMS1-D11-Pad25)") (class "Default")
      (node (ref "MMS1") (pin "25") (pinfunction "D11_25") (pintype "bidirectional"))
    )
    (net (code "137") (name "unconnected-(MMS1-D12-Pad24)") (class "Default")
      (node (ref "MMS1") (pin "24") (pinfunction "D12_24") (pintype "bidirectional"))
    )
    (net (code "138") (name "unconnected-(MMS1-D13-Pad23)") (class "Default")
      (node (ref "MMS1") (pin "23") (pinfunction "D13_23") (pintype "bidirectional"))
    )
    (net (code "139") (name "unconnected-(MMS1-RES-Pad1)") (class "Default")
      (node (ref "MMS1") (pin "1") (pinfunction "RES_1") (pintype "bidirectional"))
    )
    (net (code "140") (name "unconnected-(MMS1-RX-Pad20)") (class "Default")
      (node (ref "MMS1") (pin "20") (pinfunction "RX_20") (pintype "bidirectional"))
    )
    (net (code "141") (name "unconnected-(MMS1-TX-Pad19)") (class "Default")
      (node (ref "MMS1") (pin "19") (pinfunction "TX_19") (pintype "bidirectional"))
    )
    (net (code "142") (name "unconnected-(MMS1-VIN-Pad6)") (class "Default")
      (node (ref "MMS1") (pin "6") (pinfunction "VIN_6") (pintype "bidirectional"))
    )
    (net (code "143") (name "unconnected-(MMS2-3.3V-Pad2)") (class "Default")
      (node (ref "MMS2") (pin "2") (pinfunction "3.3V_2") (pintype "bidirectional"))
    )
    (net (code "144") (name "unconnected-(MMS2-A0(EN1)-Pad7)") (class "Default")
      (node (ref "MMS2") (pin "7") (pinfunction "A0(EN1)_7") (pintype "bidirectional"))
    )
    (net (code "145") (name "unconnected-(MMS2-A1(EN2)-Pad8)") (class "Default")
      (node (ref "MMS2") (pin "8") (pinfunction "A1(EN2)_8") (pintype "bidirectional"))
    )
    (net (code "146") (name "unconnected-(MMS2-A4-Pad11)") (class "Default")
      (node (ref "MMS2") (pin "11") (pinfunction "A4_11") (pintype "bidirectional"))
    )
    (net (code "147") (name "unconnected-(MMS2-A5-Pad12)") (class "Default")
      (node (ref "MMS2") (pin "12") (pinfunction "A5_12") (pintype "bidirectional"))
    )
    (net (code "148") (name "unconnected-(MMS2-AREF-Pad21)") (class "Default")
      (node (ref "MMS2") (pin "21") (pinfunction "AREF_21") (pintype "bidirectional"))
    )
    (net (code "149") (name "unconnected-(MMS2-D2-Pad18)") (class "Default")
      (node (ref "MMS2") (pin "18") (pinfunction "D2_18") (pintype "bidirectional"))
    )
    (net (code "150") (name "unconnected-(MMS2-D3-Pad17)") (class "Default")
      (node (ref "MMS2") (pin "17") (pinfunction "D3_17") (pintype "bidirectional"))
    )
    (net (code "151") (name "unconnected-(MMS2-D10-Pad26)") (class "Default")
      (node (ref "MMS2") (pin "26") (pinfunction "D10_26") (pintype "bidirectional"))
    )
    (net (code "152") (name "unconnected-(MMS2-D11-Pad25)") (class "Default")
      (node (ref "MMS2") (pin "25") (pinfunction "D11_25") (pintype "bidirectional"))
    )
    (net (code "153") (name "unconnected-(MMS2-D12-Pad24)") (class "Default")
      (node (ref "MMS2") (pin "24") (pinfunction "D12_24") (pintype "bidirectional"))
    )
    (net (code "154") (name "unconnected-(MMS2-D13-Pad23)") (class "Default")
      (node (ref "MMS2") (pin "23") (pinfunction "D13_23") (pintype "bidirectional"))
    )
    (net (code "155") (name "unconnected-(MMS2-RES-Pad1)") (class "Default")
      (node (ref "MMS2") (pin "1") (pinfunction "RES_1") (pintype "bidirectional"))
    )
    (net (code "156") (name "unconnected-(MMS2-RX-Pad20)") (class "Default")
      (node (ref "MMS2") (pin "20") (pinfunction "RX_20") (pintype "bidirectional"))
    )
    (net (code "157") (name "unconnected-(MMS2-TX-Pad19)") (class "Default")
      (node (ref "MMS2") (pin "19") (pinfunction "TX_19") (pintype "bidirectional"))
    )
    (net (code "158") (name "unconnected-(MMS2-VIN-Pad6)") (class "Default")
      (node (ref "MMS2") (pin "6") (pinfunction "VIN_6") (pintype "bidirectional"))
    )
    (net (code "159") (name "unconnected-(SV1-Pad2)") (class "Default")
      (node (ref "SV1") (pin "2") (pinfunction "2_2") (pintype "passive"))
    )
    (net (code "160") (name "unconnected-(SV1-Pad3)") (class "Default")
      (node (ref "SV1") (pin "3") (pinfunction "3_3") (pintype "passive"))
    )
    (net (code "161") (name "unconnected-(SV1-Pad4)") (class "Default")
      (node (ref "SV1") (pin "4") (pinfunction "4_4") (pintype "passive"))
    )
    (net (code "162") (name "unconnected-(SV1-Pad6)") (class "Default")
      (node (ref "SV1") (pin "6") (pinfunction "6_6") (pintype "passive"))
    )
    (net (code "163") (name "unconnected-(X2B-S-Pad2)") (class "Default")
      (node (ref "X2") (pin "2") (pinfunction "S_2") (pintype "passive"))
    )
    (net (code "164") (name "unconnected-(X2C-S-Pad3)") (class "Default")
      (node (ref "X2") (pin "3") (pinfunction "S_3") (pintype "passive"))
    )
    (net (code "165") (name "unconnected-(X2D-S-Pad4)") (class "Default")
      (node (ref "X2") (pin "4") (pinfunction "S_4") (pintype "passive"))
    )
    (net (code "166") (name "unconnected-(X3B-S-Pad2)") (class "Default")
      (node (ref "X3") (pin "2") (pinfunction "S_2") (pintype "passive"))
    )
    (net (code "167") (name "unconnected-(X3C-S-Pad3)") (class "Default")
      (node (ref "X3") (pin "3") (pinfunction "S_3") (pintype "passive"))
    )
    (net (code "168") (name "unconnected-(X3D-S-Pad4)") (class "Default")
      (node (ref "X3") (pin "4") (pinfunction "S_4") (pintype "passive"))
    )
    (net (code "169") (name "unconnected-(X10B-S-Pad2)") (class "Default")
      (node (ref "X10") (pin "2") (pinfunction "S_2") (pintype "passive"))
    )
  )
)
